# STM32f407layout.net
KiCad netlist of a schematic drawn in EAGLE
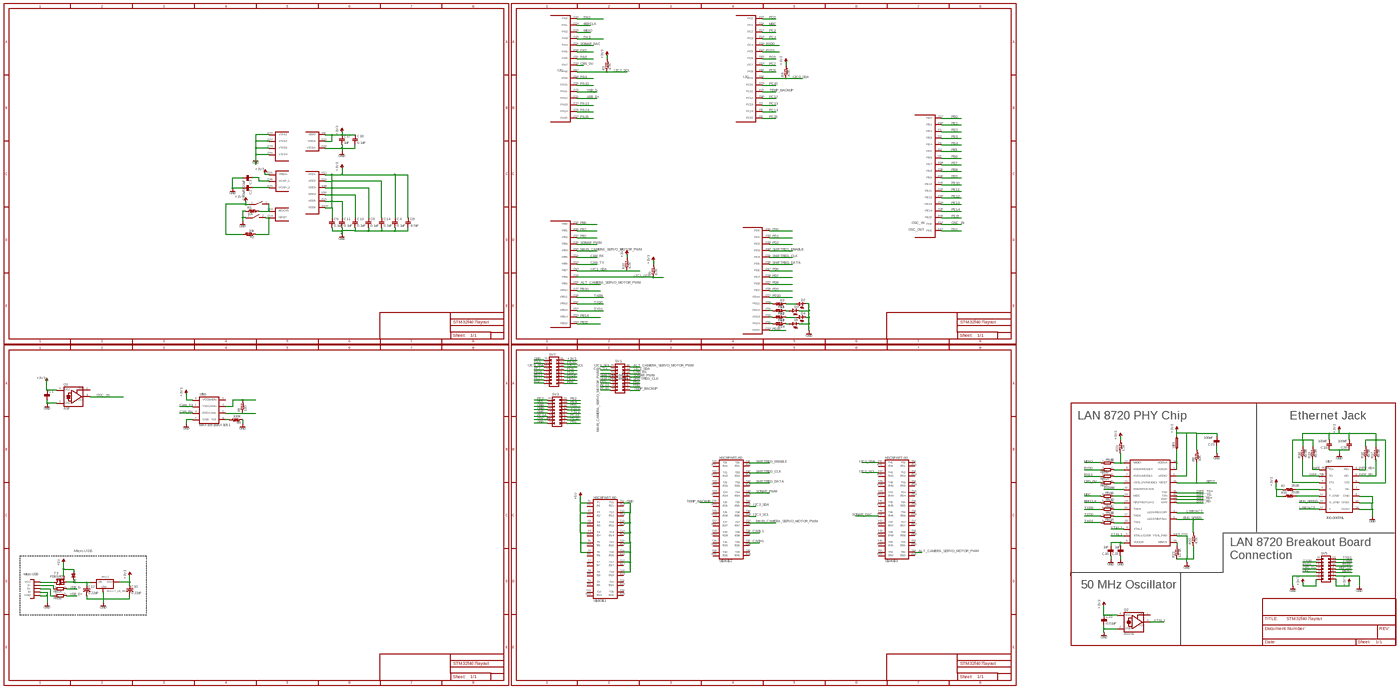
[diagram p0: schematic, sheet 1, overview]
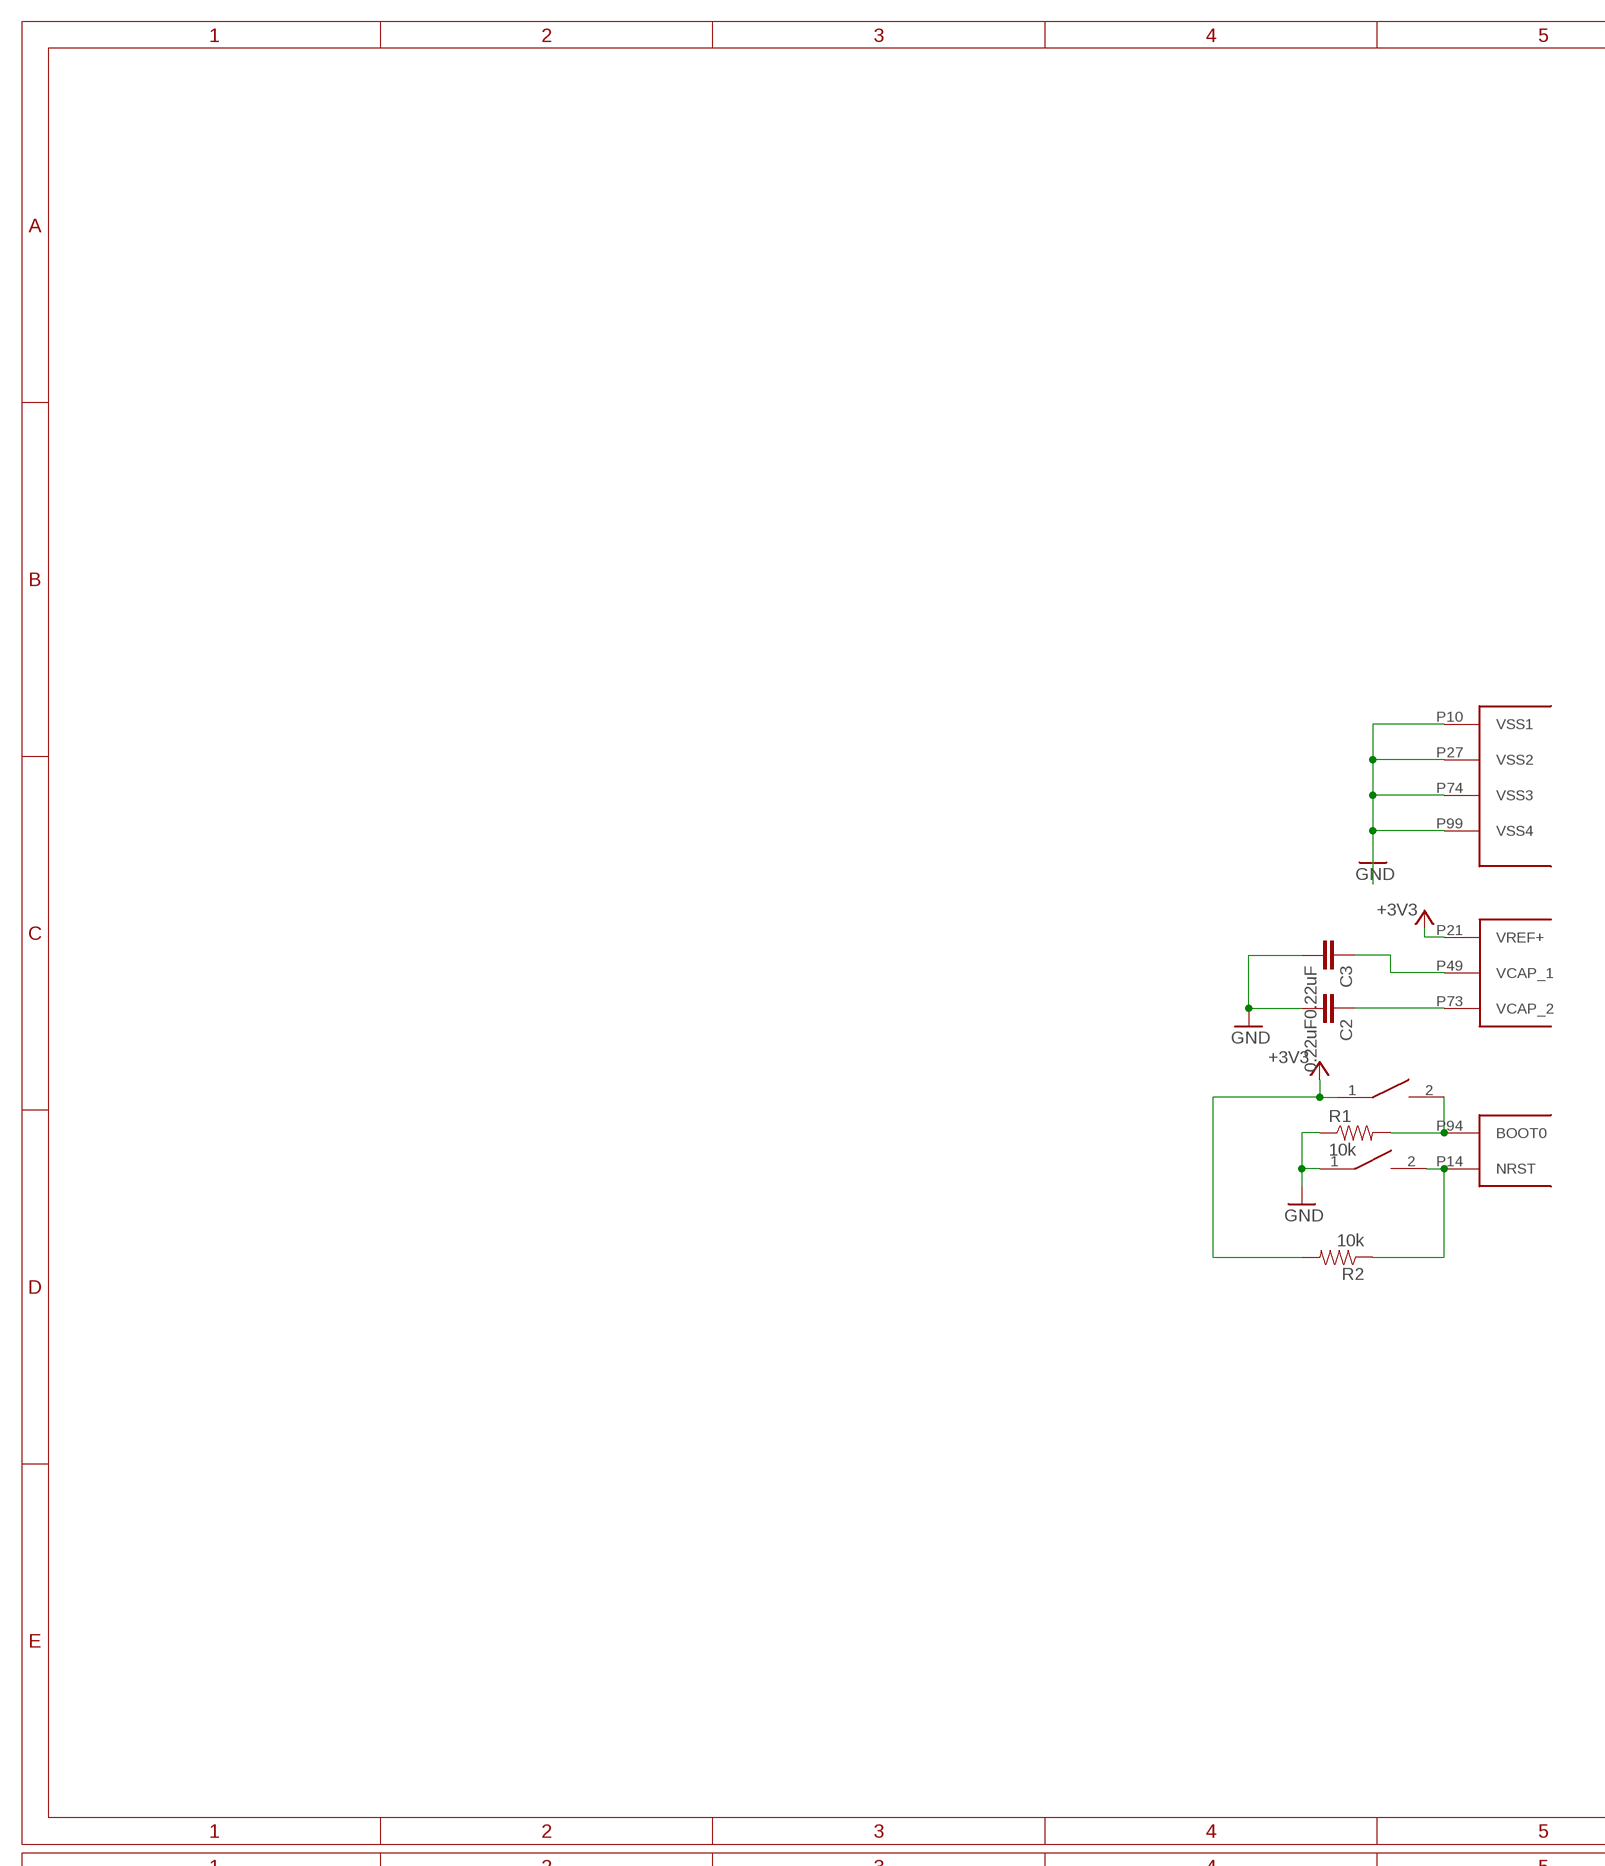
[diagram p1: schematic, sheet 1, part 1 of 7]
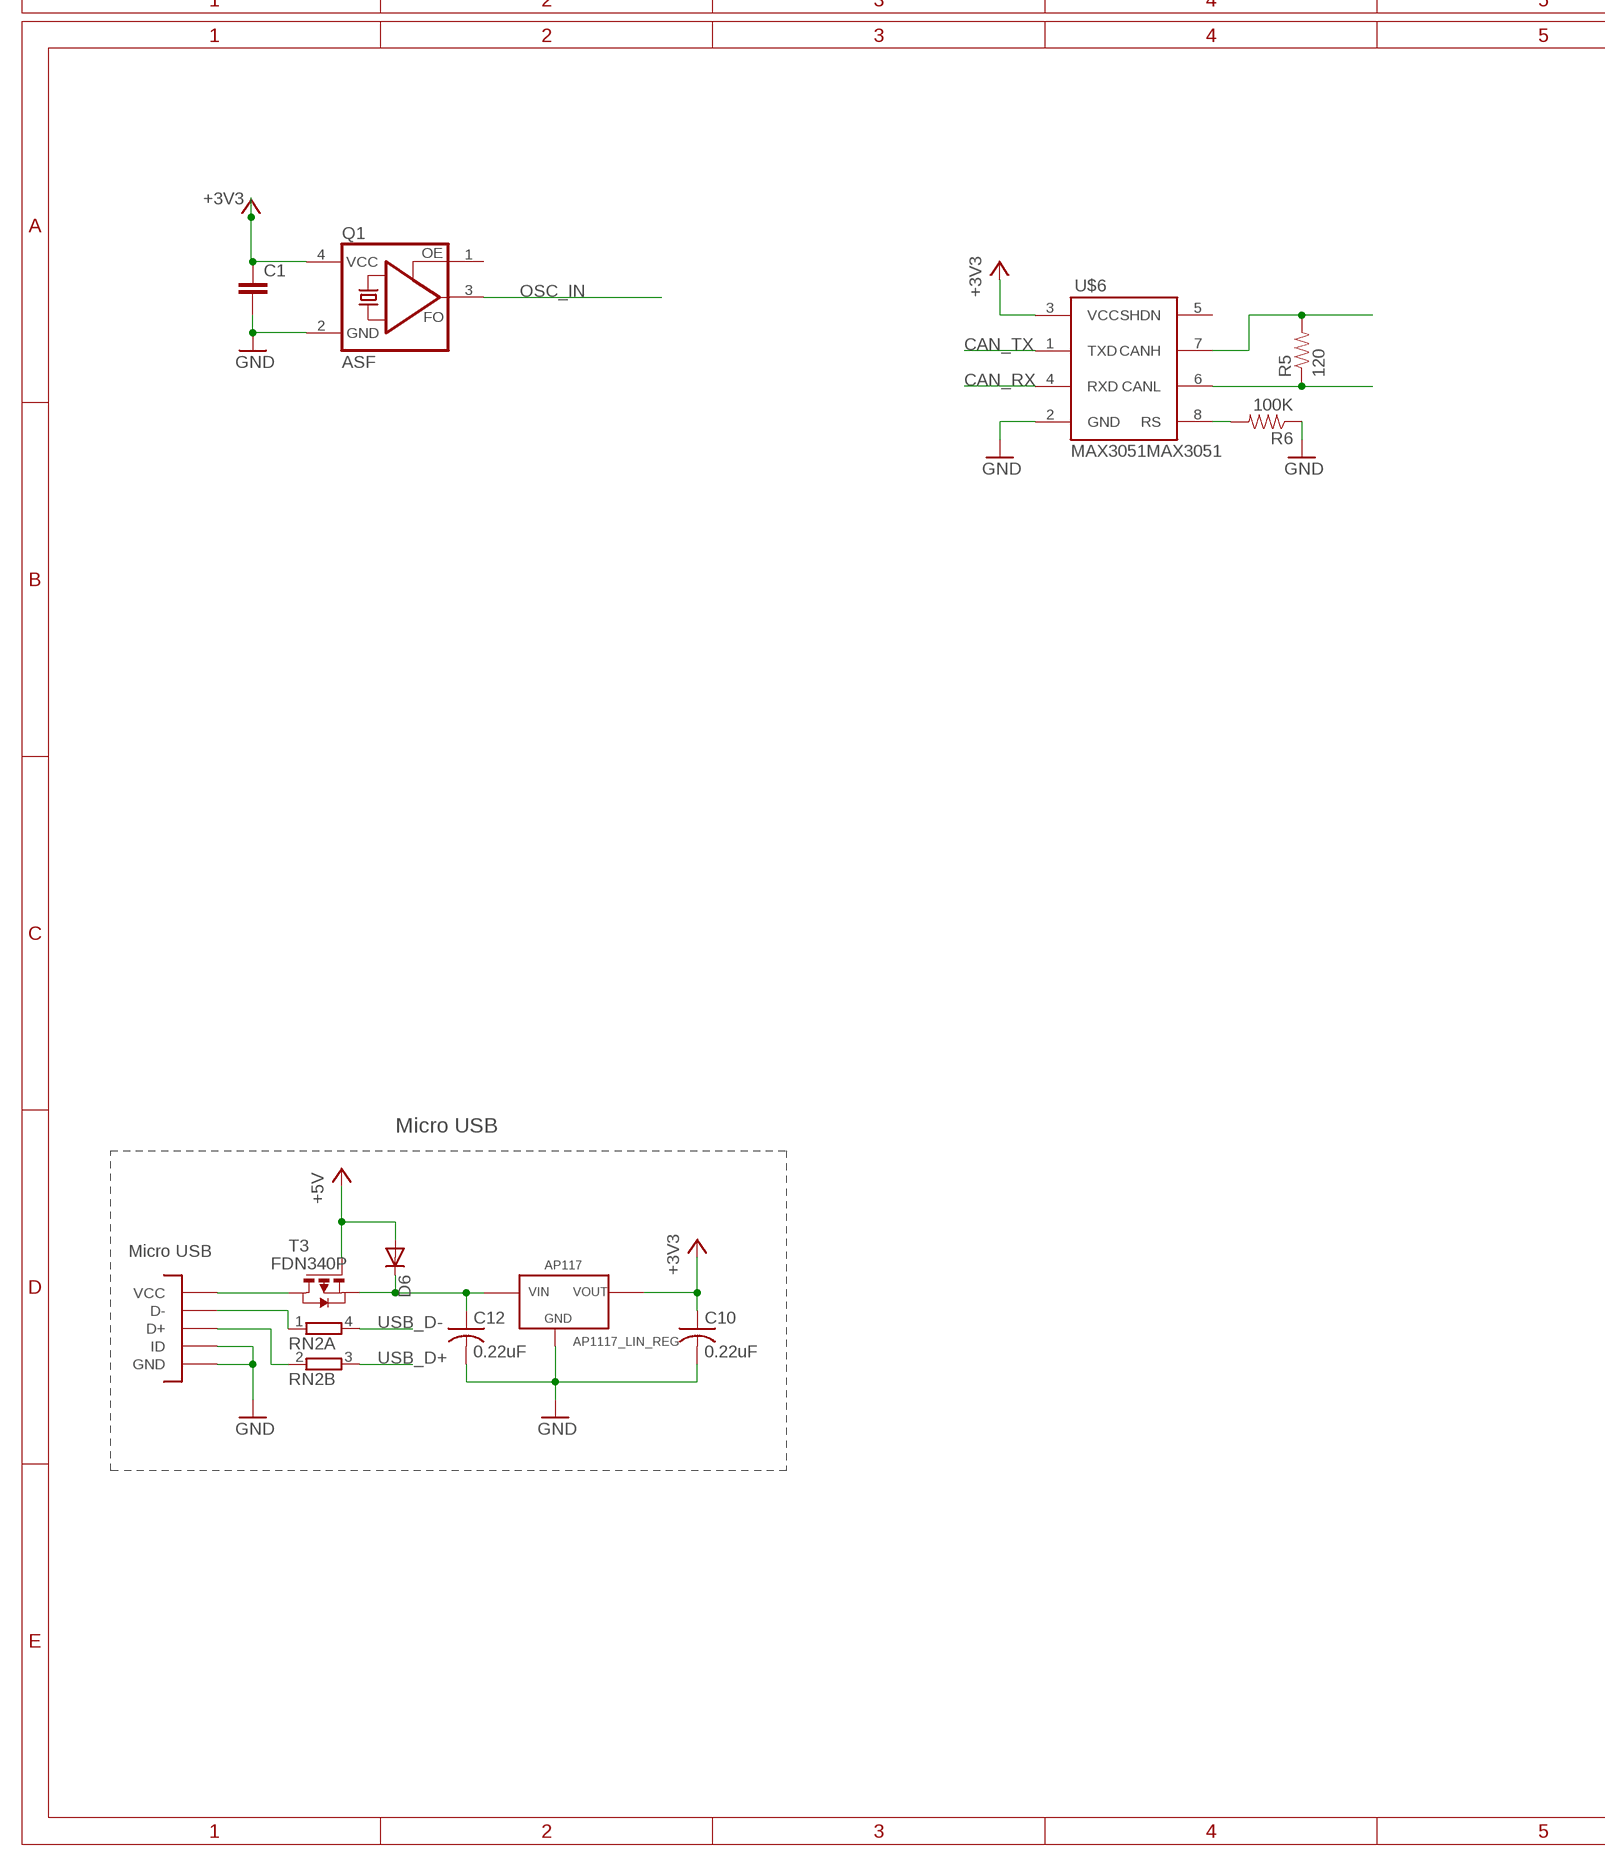
[diagram p2: schematic, sheet 1, part 2 of 7]
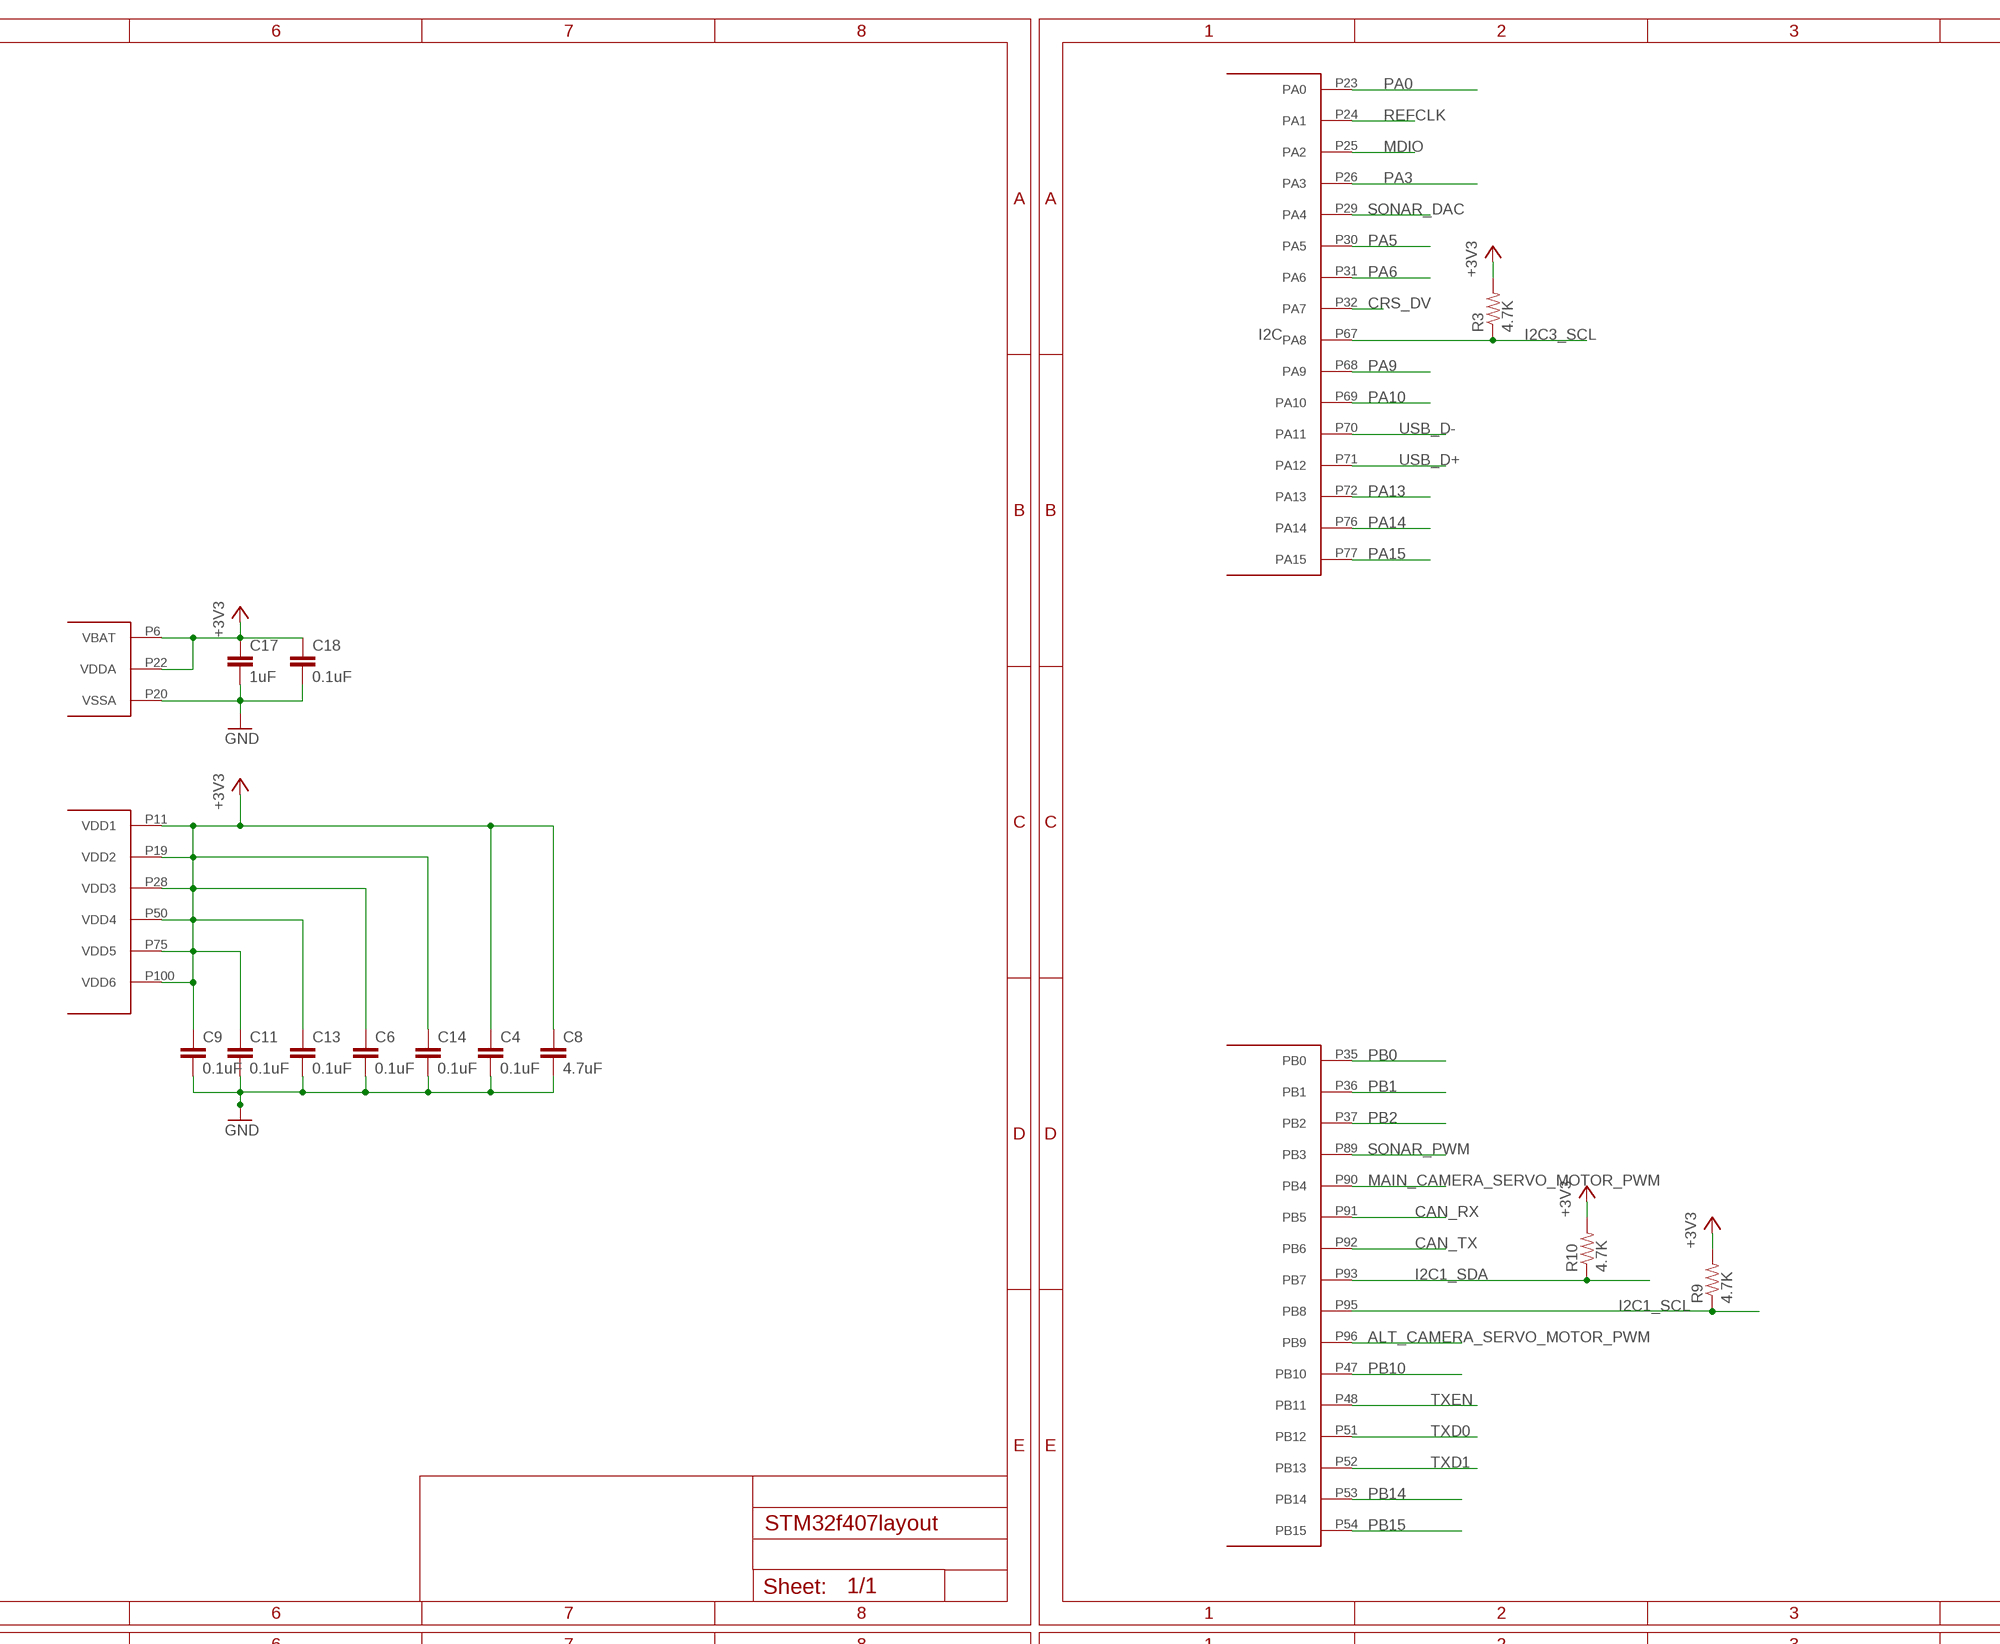
[diagram p3: schematic, sheet 1, part 3 of 7]
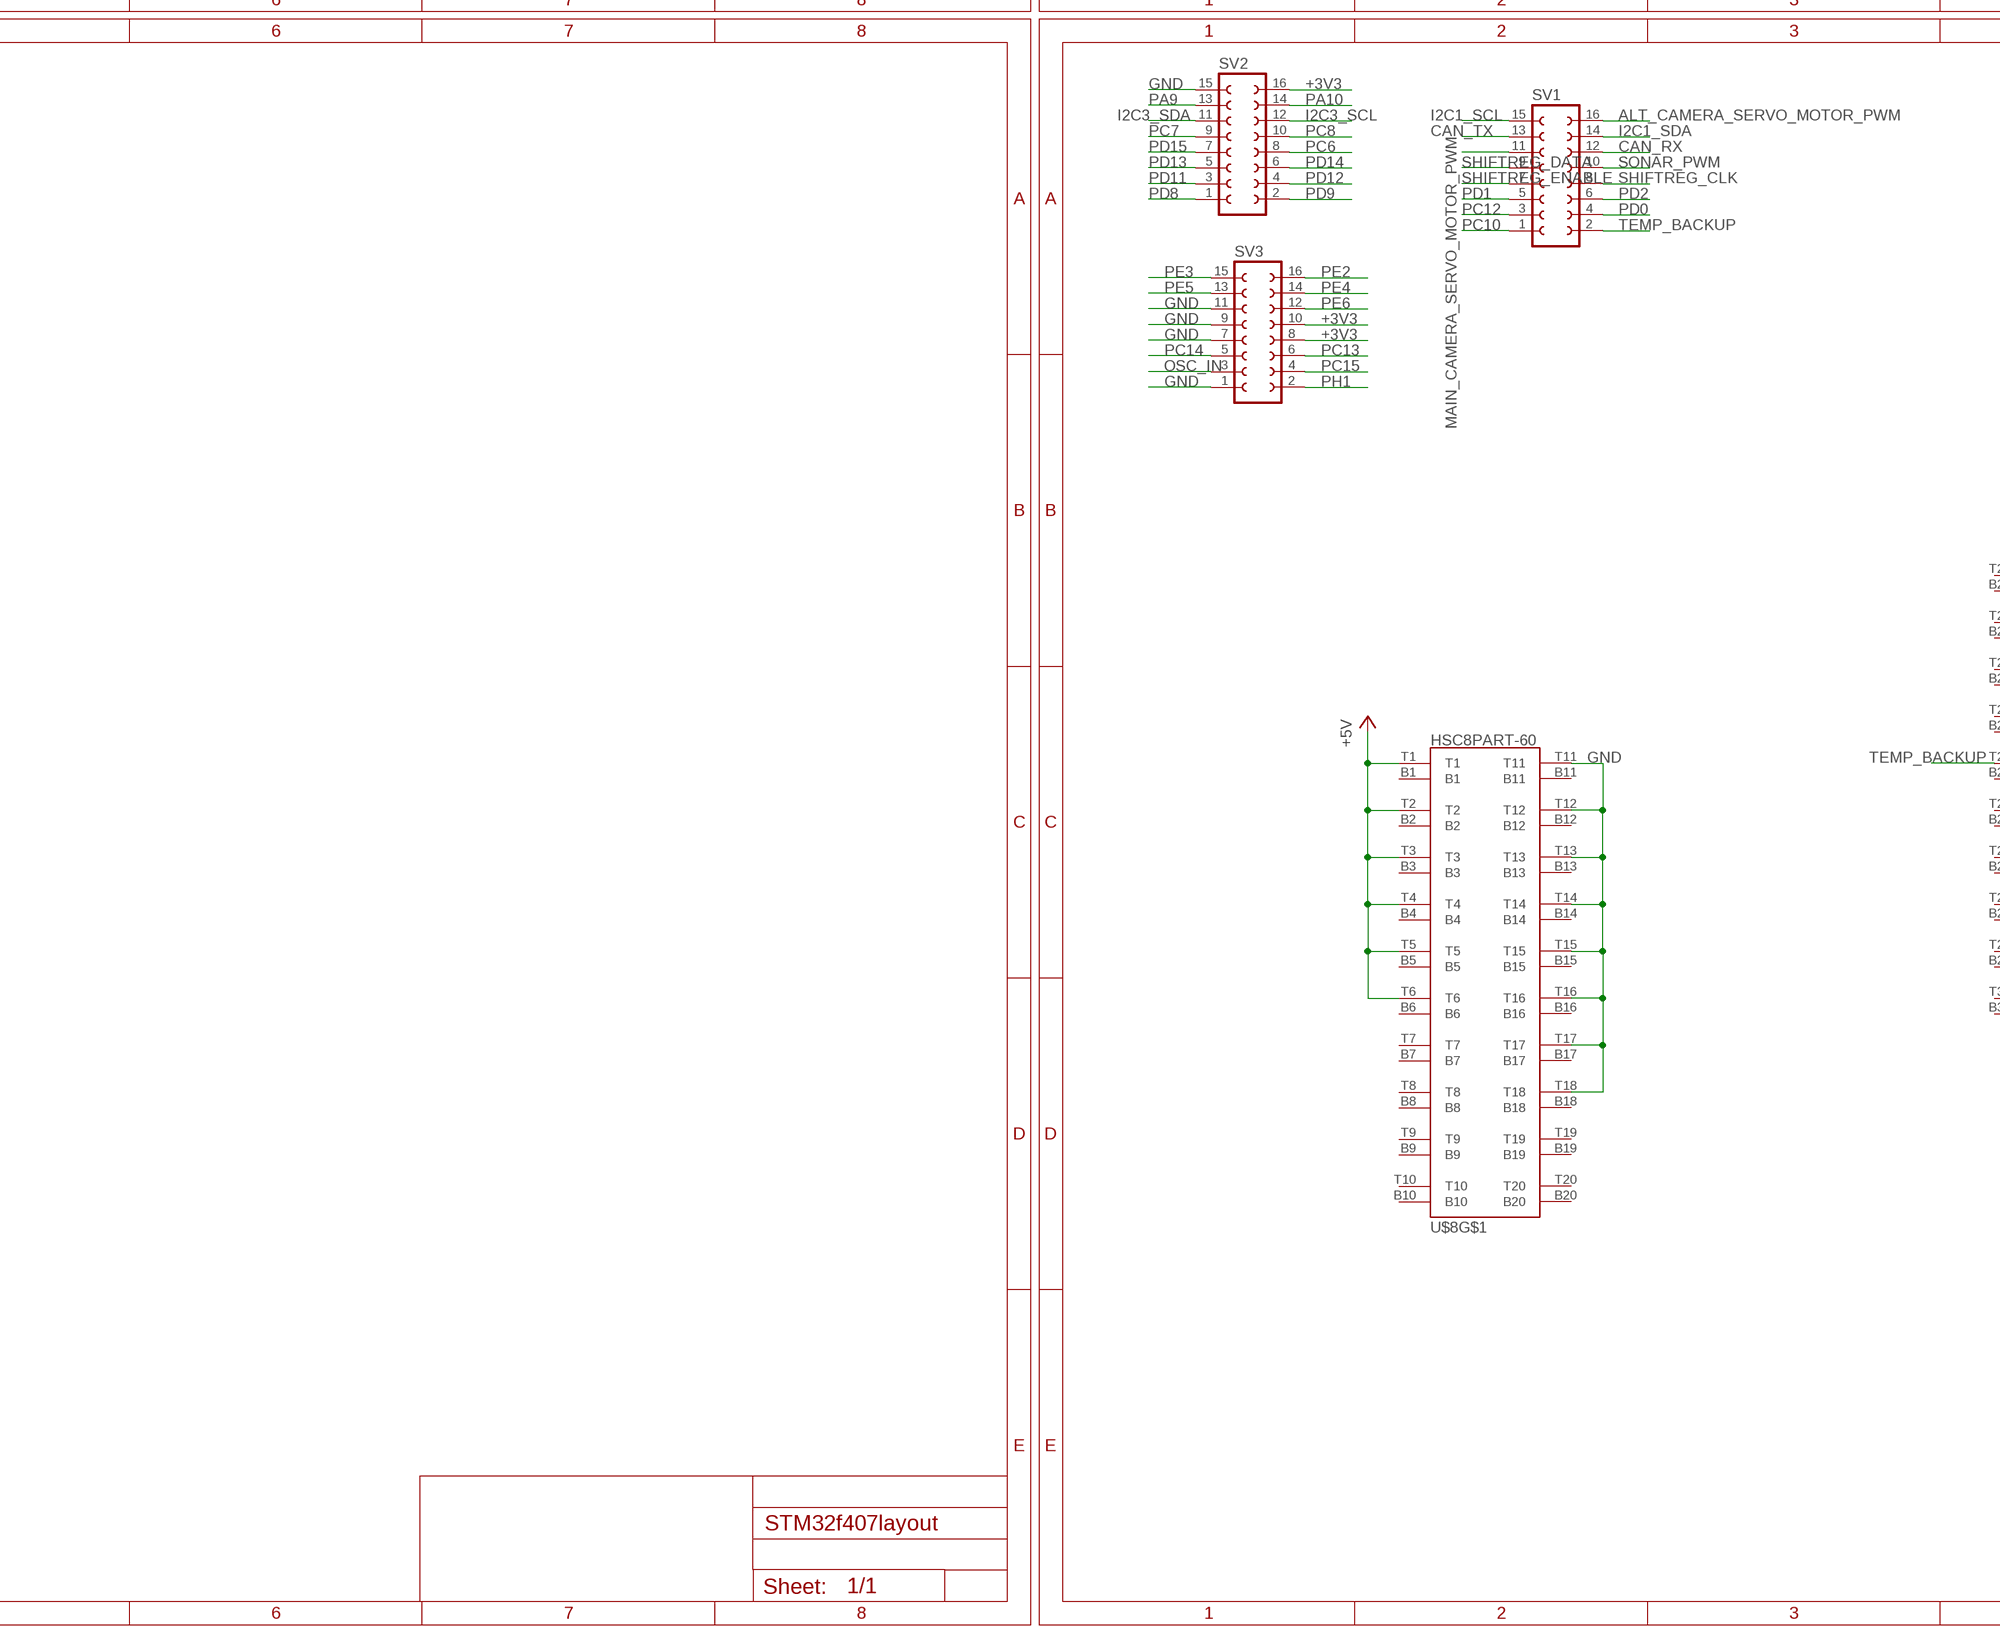
[diagram p4: schematic, sheet 1, part 4 of 7]
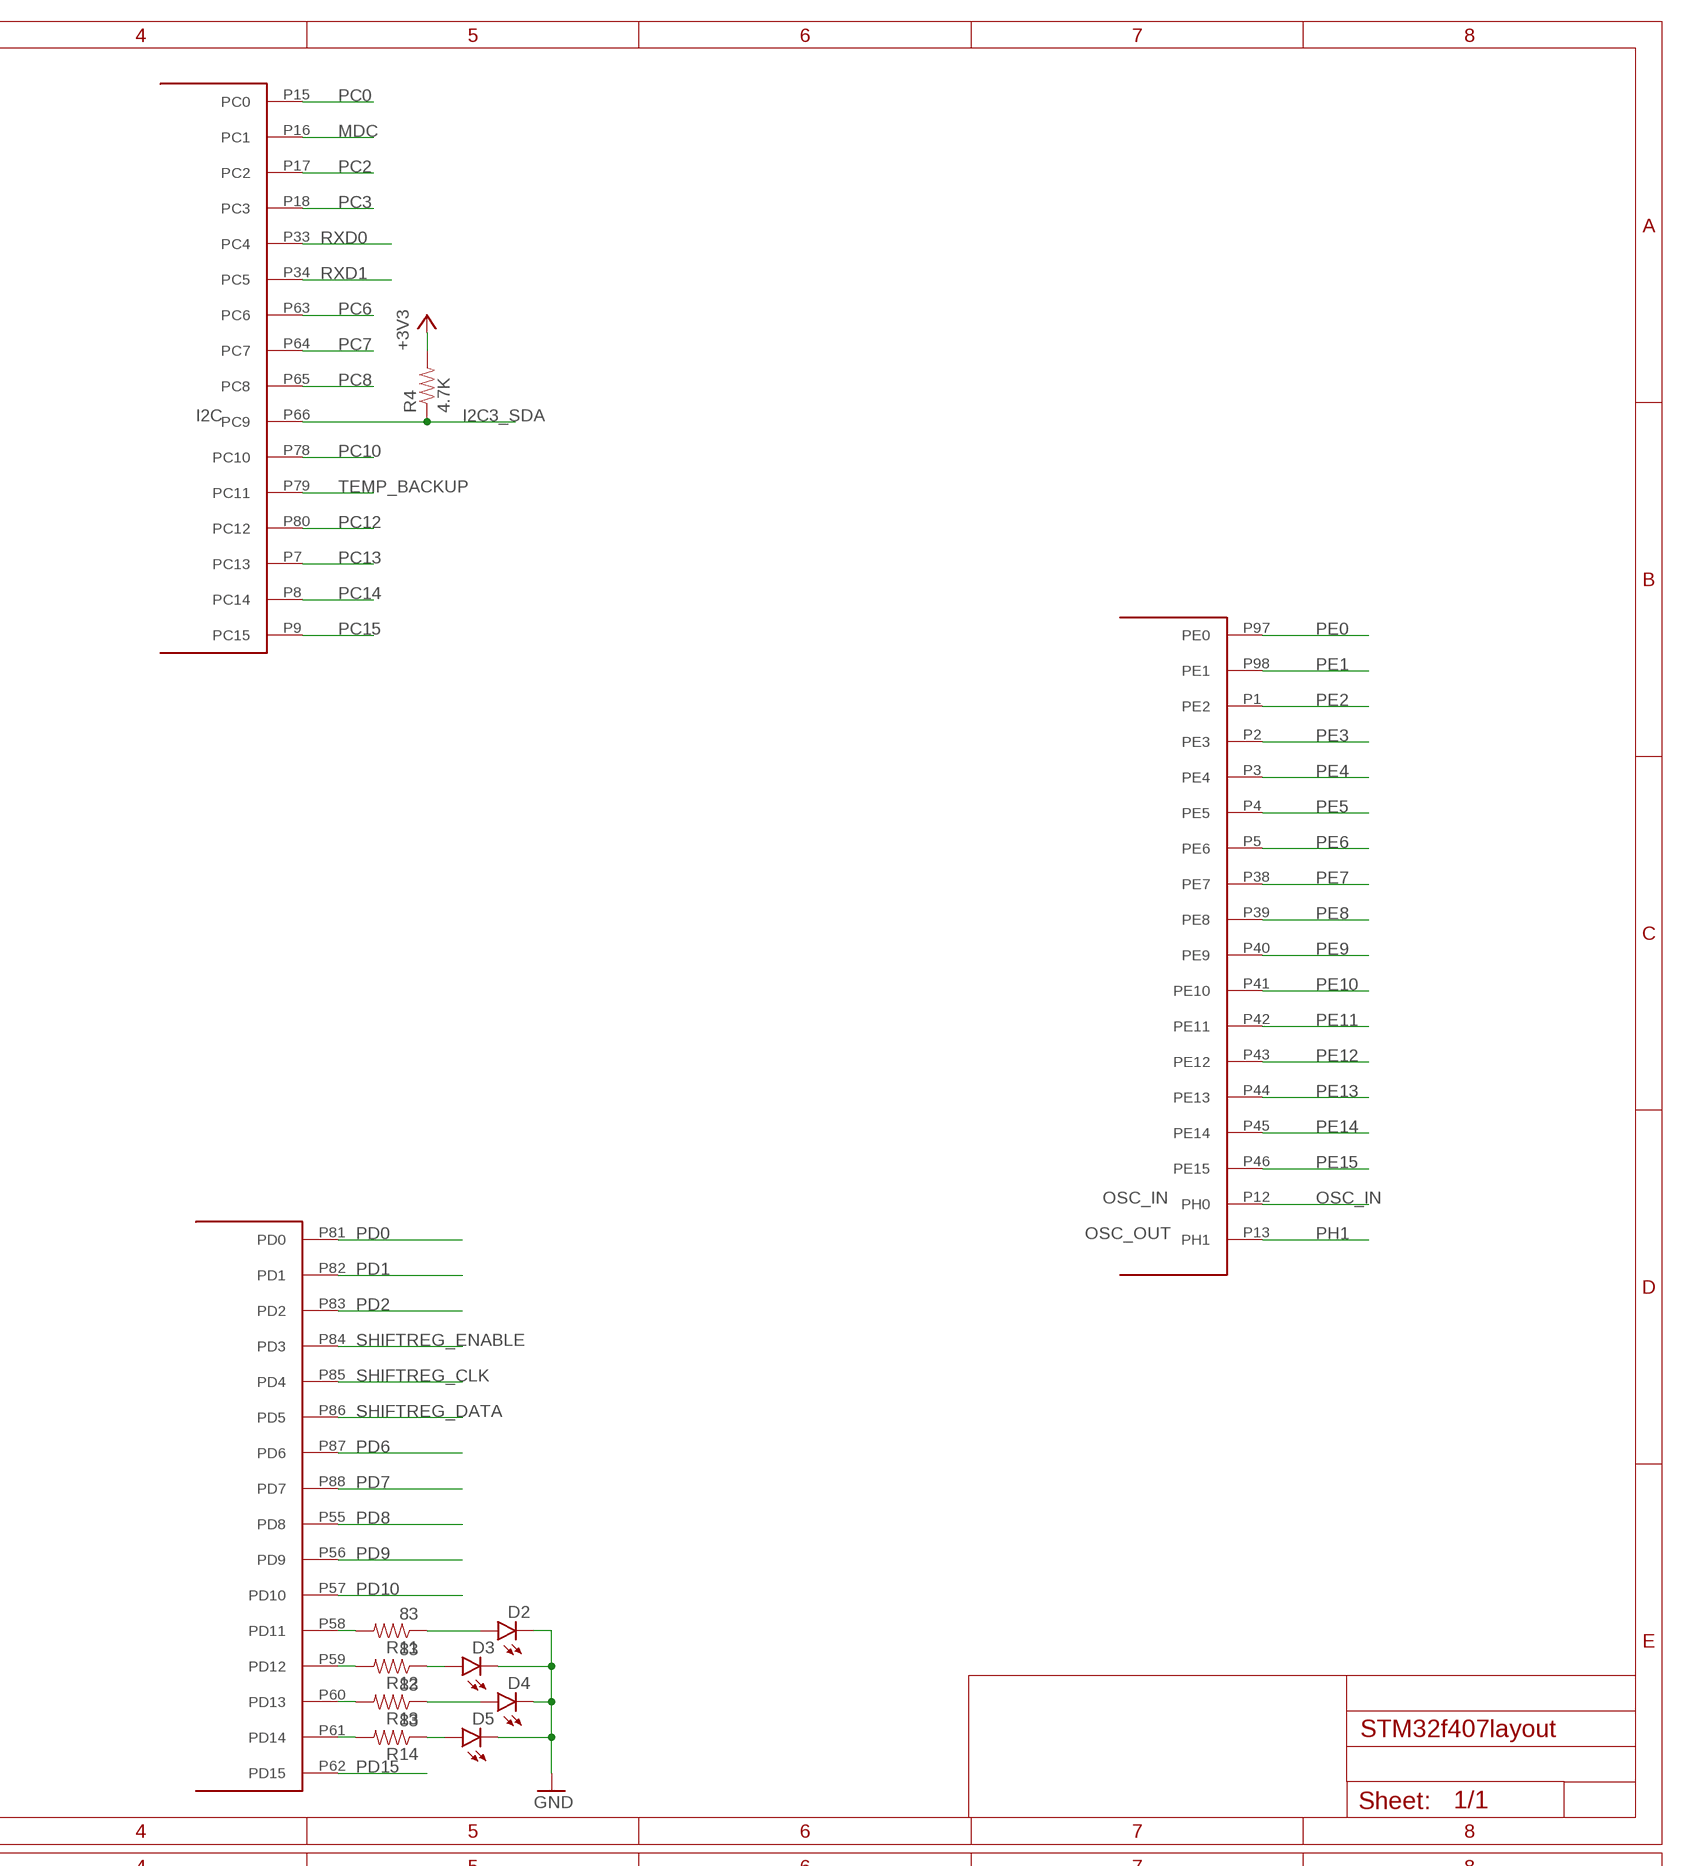
[diagram p5: schematic, sheet 1, part 5 of 7]
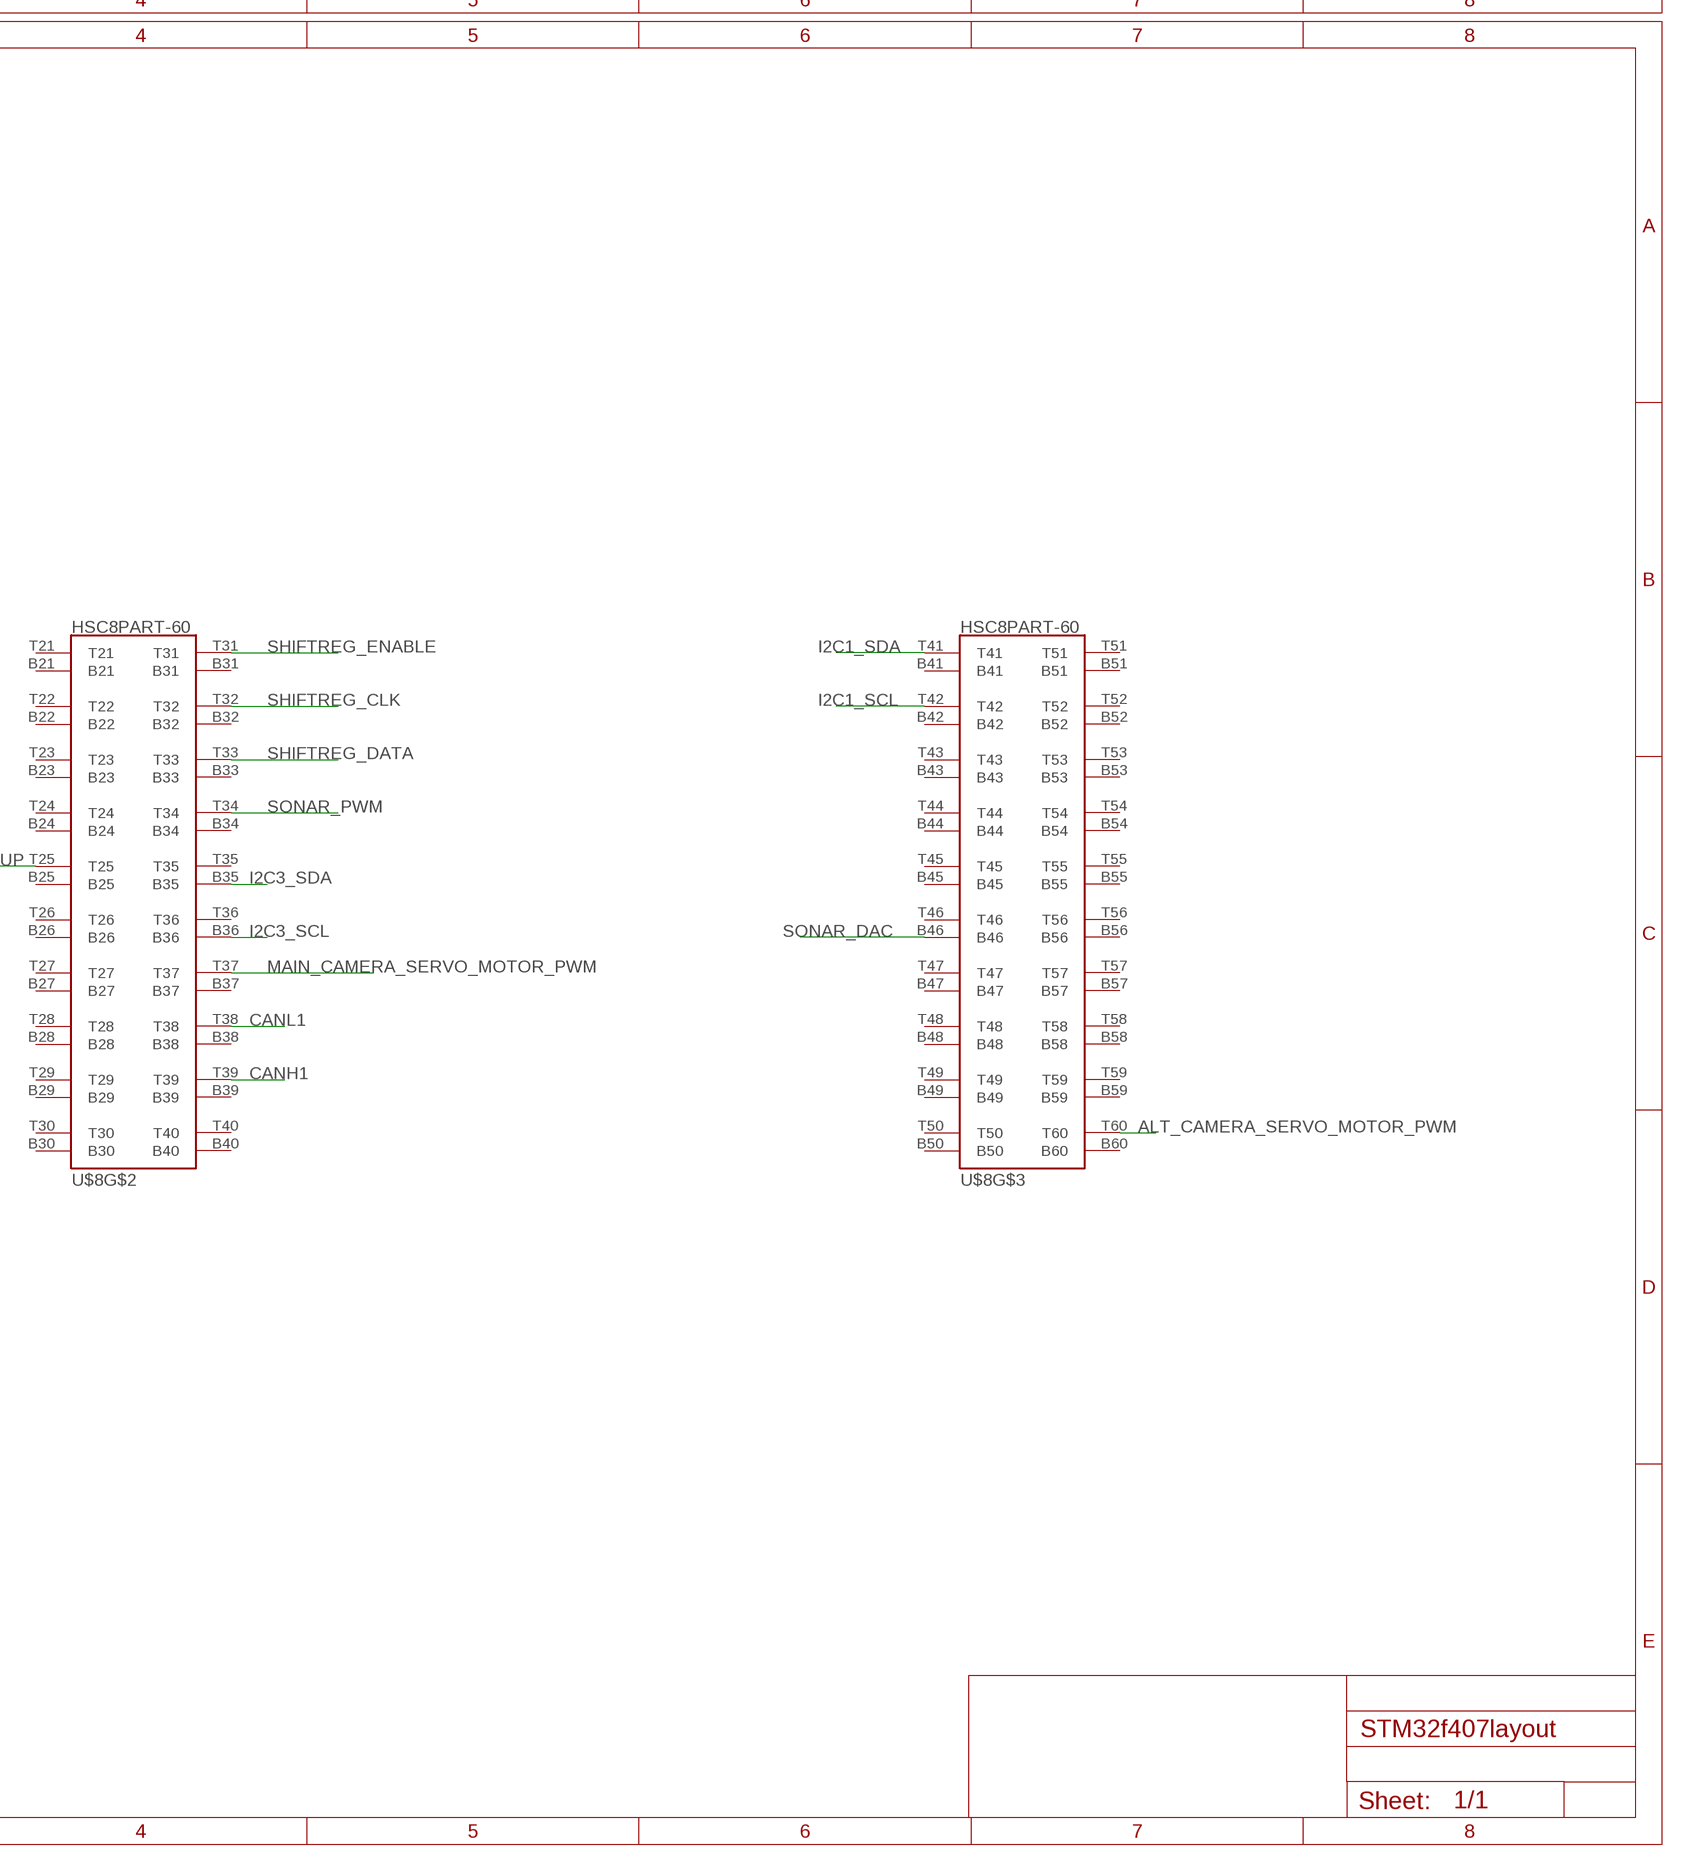
[diagram p6: schematic, sheet 1, part 6 of 7]
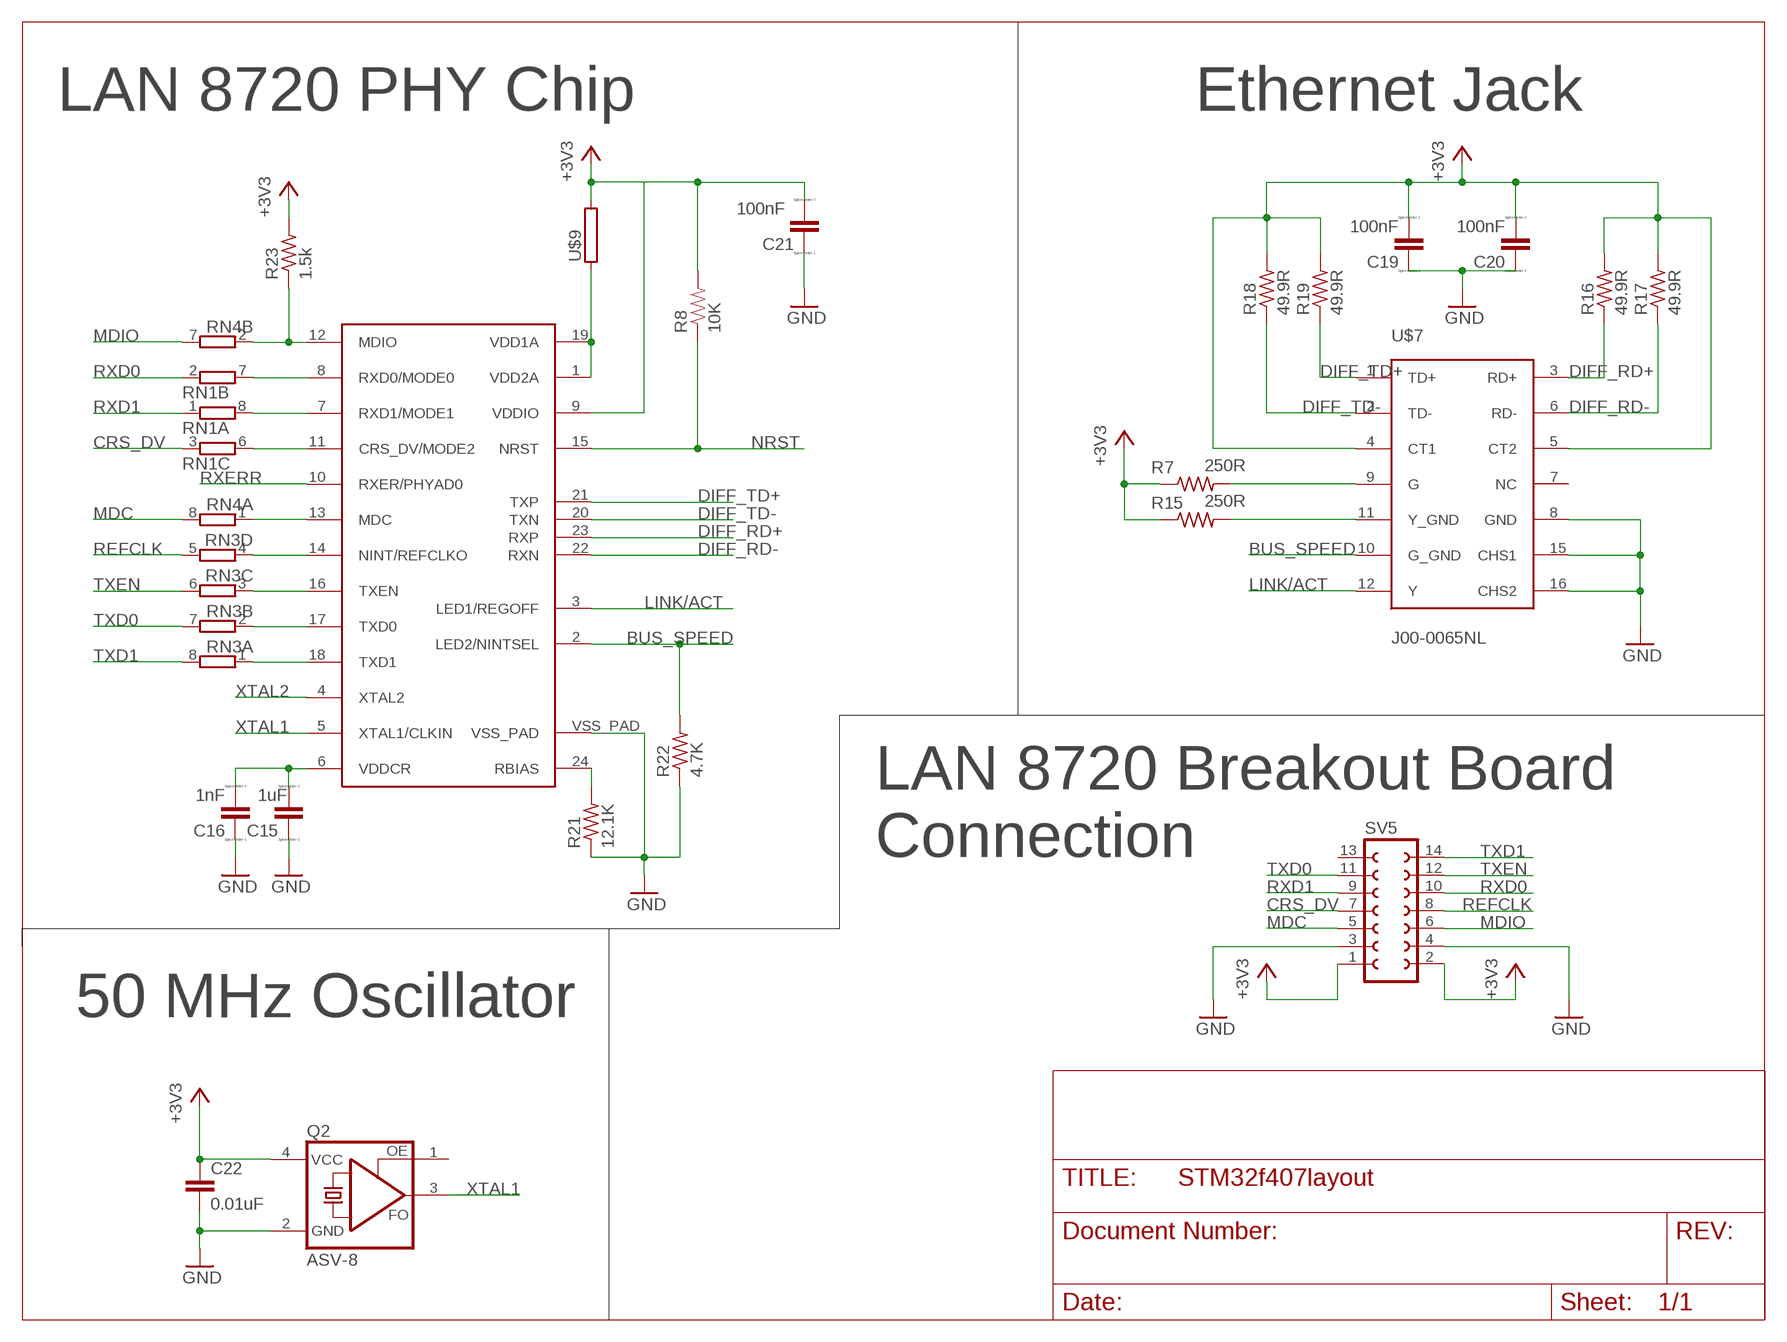
[diagram p7: schematic, sheet 1, part 7 of 7]

(export (version "E")
  (design (tool "Eeschema 10.0.6"))
  (components
    (comp (ref "C1")
      (value "CAP0603-CAP")
      (footprint "eagle-import:0603-CAP")
      (libsource (lib "eagle-import") (part "CAP0603-CAP"))
    )
    (comp (ref "C2")
      (value "0.22uF")
      (footprint "eagle-import:0603-CAP")
      (libsource (lib "eagle-import") (part "CAP0603-CAP"))
    )
    (comp (ref "C3")
      (value "0.22uF")
      (footprint "eagle-import:0603-CAP")
      (libsource (lib "eagle-import") (part "CAP0603-CAP"))
    )
    (comp (ref "C4")
      (value "0.1uF")
      (footprint "eagle-import:0603-CAP")
      (libsource (lib "eagle-import") (part "CAP0603-CAP"))
    )
    (comp (ref "C6")
      (value "0.1uF")
      (footprint "eagle-import:0603-CAP")
      (libsource (lib "eagle-import") (part "CAP0603-CAP"))
    )
    (comp (ref "C8")
      (value "4.7uF")
      (footprint "eagle-import:0603-CAP")
      (libsource (lib "eagle-import") (part "CAP0603-CAP"))
    )
    (comp (ref "C9")
      (value "0.1uF")
      (footprint "eagle-import:0603-CAP")
      (libsource (lib "eagle-import") (part "CAP0603-CAP"))
    )
    (comp (ref "C10")
      (value "0.22uF")
      (footprint "eagle-import:C0603")
      (libsource (lib "eagle-import") (part "C-USC0603"))
    )
    (comp (ref "C11")
      (value "0.1uF")
      (footprint "eagle-import:0603-CAP")
      (libsource (lib "eagle-import") (part "CAP0603-CAP"))
    )
    (comp (ref "C12")
      (value "0.22uF")
      (footprint "eagle-import:C0603")
      (libsource (lib "eagle-import") (part "C-USC0603"))
    )
    (comp (ref "C13")
      (value "0.1uF")
      (footprint "eagle-import:0603-CAP")
      (libsource (lib "eagle-import") (part "CAP0603-CAP"))
    )
    (comp (ref "C14")
      (value "0.1uF")
      (footprint "eagle-import:0603-CAP")
      (libsource (lib "eagle-import") (part "CAP0603-CAP"))
    )
    (comp (ref "C15")
      (value "1uF")
      (footprint "eagle-import:C0603")
      (libsource (lib "eagle-import") (part "CC0603"))
    )
    (comp (ref "C16")
      (value "1nF")
      (footprint "eagle-import:C0603")
      (libsource (lib "eagle-import") (part "CC0603"))
    )
    (comp (ref "C17")
      (value "1uF")
      (footprint "eagle-import:0603-CAP")
      (libsource (lib "eagle-import") (part "CAP0603-CAP"))
    )
    (comp (ref "C18")
      (value "0.1uF")
      (footprint "eagle-import:0603-CAP")
      (libsource (lib "eagle-import") (part "CAP0603-CAP"))
    )
    (comp (ref "C19")
      (value "100nF")
      (footprint "eagle-import:C0603")
      (libsource (lib "eagle-import") (part "CC0603"))
    )
    (comp (ref "C20")
      (value "100nF")
      (footprint "eagle-import:C0603")
      (libsource (lib "eagle-import") (part "CC0603"))
    )
    (comp (ref "C21")
      (value "100nF")
      (footprint "eagle-import:C0603")
      (libsource (lib "eagle-import") (part "CC0603"))
    )
    (comp (ref "C22")
      (value "0.01uF")
      (footprint "eagle-import:C0603")
      (libsource (lib "eagle-import") (part "C-EUC0603"))
    )
    (comp (ref "D2")
      (value "LED0603")
      (footprint "eagle-import:LED-0603")
      (libsource (lib "eagle-import") (part "LED0603"))
    )
    (comp (ref "D3")
      (value "LED0603")
      (footprint "eagle-import:LED-0603")
      (libsource (lib "eagle-import") (part "LED0603"))
    )
    (comp (ref "D4")
      (value "LED0603")
      (footprint "eagle-import:LED-0603")
      (libsource (lib "eagle-import") (part "LED0603"))
    )
    (comp (ref "D5")
      (value "LED0603")
      (footprint "eagle-import:LED-0603")
      (libsource (lib "eagle-import") (part "LED0603"))
    )
    (comp (ref "D6")
      (value "DIODE-DO-214AC")
      (footprint "eagle-import:DO-214AC")
      (libsource (lib "eagle-import") (part "DIODE-DO-214AC"))
    )
    (comp (ref "Q1")
      (value "ASF")
      (footprint "eagle-import:ASF")
      (libsource (lib "eagle-import") (part "ASF"))
    )
    (comp (ref "Q2")
      (value "ASV-8")
      (footprint "eagle-import:ASF")
      (libsource (lib "eagle-import") (part "MicroBoard_ASF"))
    )
    (comp (ref "R1")
      (value "10k")
      (footprint "eagle-import:0603-RES")
      (libsource (lib "eagle-import") (part "RESISTOR0603-RES"))
    )
    (comp (ref "R2")
      (value "10k")
      (footprint "eagle-import:0603-RES")
      (libsource (lib "eagle-import") (part "RESISTOR0603-RES"))
    )
    (comp (ref "R3")
      (value "4.7K")
      (footprint "eagle-import:0603-RES")
      (libsource (lib "eagle-import") (part "RESISTOR0603-RES"))
    )
    (comp (ref "R4")
      (value "4.7K")
      (footprint "eagle-import:0603-RES")
      (libsource (lib "eagle-import") (part "RESISTOR0603-RES"))
    )
    (comp (ref "R5")
      (value "120")
      (footprint "eagle-import:0603-RES")
      (libsource (lib "eagle-import") (part "RESISTOR0603-RES"))
    )
    (comp (ref "R6")
      (value "100K")
      (footprint "eagle-import:0603-RES")
      (libsource (lib "eagle-import") (part "RESISTOR0603-RES"))
    )
    (comp (ref "R7")
      (value "250R")
      (footprint "eagle-import:R0603")
      (libsource (lib "eagle-import") (part "R-US_R0603"))
    )
    (comp (ref "R8")
      (value "10K")
      (footprint "eagle-import:0603-RES")
      (libsource (lib "eagle-import") (part "RESISTOR0603-RES"))
    )
    (comp (ref "R9")
      (value "4.7K")
      (footprint "eagle-import:0603-RES")
      (libsource (lib "eagle-import") (part "RESISTOR0603-RES"))
    )
    (comp (ref "R10")
      (value "4.7K")
      (footprint "eagle-import:0603-RES")
      (libsource (lib "eagle-import") (part "RESISTOR0603-RES"))
    )
    (comp (ref "R11")
      (value "83")
      (footprint "eagle-import:0603-RES")
      (libsource (lib "eagle-import") (part "RESISTOR0603-RES"))
    )
    (comp (ref "R12")
      (value "83")
      (footprint "eagle-import:0603-RES")
      (libsource (lib "eagle-import") (part "RESISTOR0603-RES"))
    )
    (comp (ref "R13")
      (value "83")
      (footprint "eagle-import:0603-RES")
      (libsource (lib "eagle-import") (part "RESISTOR0603-RES"))
    )
    (comp (ref "R14")
      (value "83")
      (footprint "eagle-import:0603-RES")
      (libsource (lib "eagle-import") (part "RESISTOR0603-RES"))
    )
    (comp (ref "R15")
      (value "250R")
      (footprint "eagle-import:R0603")
      (libsource (lib "eagle-import") (part "R-US_R0603"))
    )
    (comp (ref "R16")
      (value "49.9R")
      (footprint "eagle-import:R0603")
      (libsource (lib "eagle-import") (part "R-US_R0603"))
    )
    (comp (ref "R17")
      (value "49.9R")
      (footprint "eagle-import:R0603")
      (libsource (lib "eagle-import") (part "R-US_R0603"))
    )
    (comp (ref "R18")
      (value "49.9R")
      (footprint "eagle-import:R0603")
      (libsource (lib "eagle-import") (part "R-US_R0603"))
    )
    (comp (ref "R19")
      (value "49.9R")
      (footprint "eagle-import:R0603")
      (libsource (lib "eagle-import") (part "R-US_R0603"))
    )
    (comp (ref "R21")
      (value "12.1K")
      (footprint "eagle-import:R0603")
      (libsource (lib "eagle-import") (part "R-US_R0603"))
    )
    (comp (ref "R22")
      (value "4.7K")
      (footprint "eagle-import:R0603")
      (libsource (lib "eagle-import") (part "R-US_R0603"))
    )
    (comp (ref "R23")
      (value "1.5k")
      (footprint "eagle-import:R0603")
      (libsource (lib "eagle-import") (part "R-US_R0603"))
    )
    (comp (ref "RN1")
      (value "4R-NCAY16")
      (footprint "eagle-import:CAY16")
      (libsource (lib "eagle-import") (part "4R-NCAY16"))
    )
    (comp (ref "RN2")
      (value "2R-NEXBV4V")
      (footprint "eagle-import:EXBV4V")
      (fields (field (name "MF") "Rohm Semiconductor") (field (name "MPN") "MNR12ERAPJ220"))
      (libsource (lib "eagle-import") (part "2R-NEXBV4V"))
    )
    (comp (ref "RN3")
      (value "4R-NCAY16")
      (footprint "eagle-import:CAY16")
      (libsource (lib "eagle-import") (part "4R-NCAY16"))
    )
    (comp (ref "RN4")
      (value "4R-NCAY16")
      (footprint "eagle-import:CAY16")
      (libsource (lib "eagle-import") (part "4R-NCAY16"))
    )
    (comp (ref "SV1")
      (value "FE08-2")
      (footprint "eagle-import:FE08-2")
      (libsource (lib "eagle-import") (part "FE08-2"))
    )
    (comp (ref "SV2")
      (value "FE08-2")
      (footprint "eagle-import:FE08-2")
      (libsource (lib "eagle-import") (part "FE08-2"))
    )
    (comp (ref "SV3")
      (value "FE08-2")
      (footprint "eagle-import:FE08-2")
      (libsource (lib "eagle-import") (part "FE08-2"))
    )
    (comp (ref "SV5")
      (value "FE07-2")
      (footprint "eagle-import:FE07-2")
      (libsource (lib "eagle-import") (part "FE07-2"))
    )
    (comp (ref "T3")
      (value "FDN340P")
      (footprint "eagle-import:SOT-23")
      (libsource (lib "eagle-import") (part "FDN340P"))
    )
    (comp (ref "T4")
      (value "AP1117_LIN_REG")
      (footprint "eagle-import:SOT223")
      (libsource (lib "eagle-import") (part "AP1117_LIN_REG"))
    )
    (comp (ref "U$1")
      (value "STM32F4")
      (footprint "eagle-import:LQFP100")
      (libsource (lib "eagle-import") (part "STM32F4"))
    )
    (comp (ref "U$2")
      (value "SWITCH")
      (footprint "eagle-import:SW_2512")
      (libsource (lib "eagle-import") (part "SWITCH"))
    )
    (comp (ref "U$3")
      (value "SWITCH")
      (footprint "eagle-import:SW_2512")
      (libsource (lib "eagle-import") (part "SWITCH"))
    )
    (comp (ref "U$4")
      (value "LAN8720LAN8720")
      (footprint "eagle-import:24-QFN")
      (libsource (lib "eagle-import") (part "LAN8720LAN8720"))
    )
    (comp (ref "U$5")
      (value "MICROUSB")
      (footprint "eagle-import:MICRO_B")
      (libsource (lib "eagle-import") (part "MICROUSB"))
    )
    (comp (ref "U$6")
      (value "MAX3051MAX3051")
      (footprint "eagle-import:SOT23-8L")
      (libsource (lib "eagle-import") (part "MAX3051MAX3051"))
    )
    (comp (ref "U$7")
      (value "J00-0065NL")
      (footprint "eagle-import:J00-0065NL")
      (libsource (lib "eagle-import") (part "J00-0065NL"))
    )
    (comp (ref "U$8")
      (value "HSC8PART-60")
      (footprint "eagle-import:HSC8-60PINOUUT")
      (libsource (lib "eagle-import") (part "HSC8PART-60"))
    )
    (comp (ref "U$9")
      (value "553-2382-1-ND")
      (footprint "eagle-import:0603")
      (libsource (lib "eagle-import") (part "553-2382-1-ND"))
    )
  )
  (nets
    (net (code "1") (name "+3V3") (class "Default")
      (node (ref "C1") (pin "1") (pinfunction "1_1") (pintype "passive"))
      (node (ref "C10") (pin "1") (pinfunction "1_1") (pintype "passive"))
      (node (ref "C11") (pin "1") (pinfunction "1_1") (pintype "passive"))
      (node (ref "C13") (pin "1") (pinfunction "1_1") (pintype "passive"))
      (node (ref "C14") (pin "1") (pinfunction "1_1") (pintype "passive"))
      (node (ref "C17") (pin "1") (pinfunction "1_1") (pintype "passive"))
      (node (ref "C18") (pin "1") (pinfunction "1_1") (pintype "passive"))
      (node (ref "C19") (pin "2") (pinfunction "2_2") (pintype "passive"))
      (node (ref "C20") (pin "2") (pinfunction "2_2") (pintype "passive"))
      (node (ref "C21") (pin "2") (pinfunction "2_2") (pintype "passive"))
      (node (ref "C22") (pin "1") (pinfunction "1_1") (pintype "passive"))
      (node (ref "C4") (pin "1") (pinfunction "1_1") (pintype "passive"))
      (node (ref "C6") (pin "1") (pinfunction "1_1") (pintype "passive"))
      (node (ref "C8") (pin "1") (pinfunction "1_1") (pintype "passive"))
      (node (ref "C9") (pin "1") (pinfunction "1_1") (pintype "passive"))
      (node (ref "Q1") (pin "4") (pinfunction "VCC_4") (pintype "power_in"))
      (node (ref "Q2") (pin "4") (pinfunction "VCC_4") (pintype "power_in"))
      (node (ref "R10") (pin "2") (pinfunction "2_2") (pintype "passive"))
      (node (ref "R15") (pin "1") (pinfunction "1_1") (pintype "passive"))
      (node (ref "R16") (pin "2") (pinfunction "2_2") (pintype "passive"))
      (node (ref "R17") (pin "2") (pinfunction "2_2") (pintype "passive"))
      (node (ref "R18") (pin "2") (pinfunction "2_2") (pintype "passive"))
      (node (ref "R19") (pin "2") (pinfunction "2_2") (pintype "passive"))
      (node (ref "R2") (pin "2") (pinfunction "2_2") (pintype "passive"))
      (node (ref "R23") (pin "2") (pinfunction "2_2") (pintype "passive"))
      (node (ref "R3") (pin "2") (pinfunction "2_2") (pintype "passive"))
      (node (ref "R4") (pin "2") (pinfunction "2_2") (pintype "passive"))
      (node (ref "R7") (pin "1") (pinfunction "1_1") (pintype "passive"))
      (node (ref "R8") (pin "2") (pinfunction "2_2") (pintype "passive"))
      (node (ref "R9") (pin "2") (pinfunction "2_2") (pintype "passive"))
      (node (ref "SV2") (pin "16") (pinfunction "16_16") (pintype "passive"))
      (node (ref "SV3") (pin "10") (pinfunction "10_10") (pintype "passive"))
      (node (ref "SV3") (pin "8") (pinfunction "8_8") (pintype "passive"))
      (node (ref "SV5") (pin "1") (pinfunction "1_1") (pintype "passive"))
      (node (ref "SV5") (pin "2") (pinfunction "2_2") (pintype "passive"))
      (node (ref "T4") (pin "TAB") (pinfunction "VOUT_TAB") (pintype "output"))
      (node (ref "T4") (pin "VOUT") (pinfunction "VOUT_VOUT") (pintype "output"))
      (node (ref "U$1") (pin "P100") (pinfunction "VDD6_P100") (pintype "bidirectional"))
      (node (ref "U$1") (pin "P11") (pinfunction "VDD1_P11") (pintype "bidirectional"))
      (node (ref "U$1") (pin "P19") (pinfunction "VDD2_P19") (pintype "bidirectional"))
      (node (ref "U$1") (pin "P21") (pinfunction "VREF+_P21") (pintype "bidirectional"))
      (node (ref "U$1") (pin "P22") (pinfunction "VDDA_P22") (pintype "bidirectional"))
      (node (ref "U$1") (pin "P28") (pinfunction "VDD3_P28") (pintype "bidirectional"))
      (node (ref "U$1") (pin "P50") (pinfunction "VDD4_P50") (pintype "bidirectional"))
      (node (ref "U$1") (pin "P6") (pinfunction "VBAT_P6") (pintype "bidirectional"))
      (node (ref "U$1") (pin "P75") (pinfunction "VDD5_P75") (pintype "bidirectional"))
      (node (ref "U$3") (pin "1") (pinfunction "P$1_1") (pintype "bidirectional"))
      (node (ref "U$4") (pin "9") (pinfunction "VDDIO_9") (pintype "bidirectional"))
      (node (ref "U$6") (pin "3") (pinfunction "VCC_3") (pintype "bidirectional"))
      (node (ref "U$7") (pin "4") (pinfunction "CT1_4") (pintype "bidirectional"))
      (node (ref "U$7") (pin "5") (pinfunction "CT2_5") (pintype "bidirectional"))
      (node (ref "U$9") (pin "2") (pinfunction "2_2") (pintype "passive"))
    )
    (net (code "2") (name "+5V") (class "Default")
      (node (ref "D6") (pin "A") (pinfunction "A_A") (pintype "passive"))
      (node (ref "T3") (pin "3") (pinfunction "G_3") (pintype "passive"))
      (node (ref "U$8") (pin "T1") (pinfunction "T1_T1") (pintype "bidirectional"))
      (node (ref "U$8") (pin "T2") (pinfunction "T2_T2") (pintype "bidirectional"))
      (node (ref "U$8") (pin "T3") (pinfunction "T3_T3") (pintype "bidirectional"))
      (node (ref "U$8") (pin "T4") (pinfunction "T4_T4") (pintype "bidirectional"))
      (node (ref "U$8") (pin "T5") (pinfunction "T5_T5") (pintype "bidirectional"))
      (node (ref "U$8") (pin "T6") (pinfunction "T6_T6") (pintype "bidirectional"))
    )
    (net (code "3") (name "/ALT_CAMERA_SERVO_MOTOR_PWM") (class "Default")
      (node (ref "SV1") (pin "16") (pinfunction "16_16") (pintype "passive"))
      (node (ref "U$1") (pin "P96") (pinfunction "PB9_P96") (pintype "bidirectional"))
      (node (ref "U$8") (pin "T60") (pinfunction "T60_T60") (pintype "bidirectional"))
    )
    (net (code "4") (name "/BUS_SPEED") (class "Default")
      (node (ref "R22") (pin "2") (pinfunction "2_2") (pintype "passive"))
      (node (ref "U$4") (pin "2") (pinfunction "LED2/NINTSEL_2") (pintype "bidirectional"))
      (node (ref "U$7") (pin "10") (pinfunction "G_GND_10") (pintype "bidirectional"))
    )
    (net (code "5") (name "/CANH1") (class "Default")
      (node (ref "R5") (pin "2") (pinfunction "2_2") (pintype "passive"))
      (node (ref "U$6") (pin "7") (pinfunction "CANH_7") (pintype "bidirectional"))
      (node (ref "U$8") (pin "T39") (pinfunction "T39_T39") (pintype "bidirectional"))
    )
    (net (code "6") (name "/CANL1") (class "Default")
      (node (ref "R5") (pin "1") (pinfunction "1_1") (pintype "passive"))
      (node (ref "U$6") (pin "6") (pinfunction "CANL_6") (pintype "bidirectional"))
      (node (ref "U$8") (pin "T38") (pinfunction "T38_T38") (pintype "bidirectional"))
    )
    (net (code "7") (name "/CAN_RX") (class "Default")
      (node (ref "SV1") (pin "12") (pinfunction "12_12") (pintype "passive"))
      (node (ref "U$1") (pin "P91") (pinfunction "PB5_P91") (pintype "bidirectional"))
      (node (ref "U$6") (pin "4") (pinfunction "RXD_4") (pintype "bidirectional"))
    )
    (net (code "8") (name "/CAN_TX") (class "Default")
      (node (ref "SV1") (pin "13") (pinfunction "13_13") (pintype "passive"))
      (node (ref "U$1") (pin "P92") (pinfunction "PB6_P92") (pintype "bidirectional"))
      (node (ref "U$6") (pin "1") (pinfunction "TXD_1") (pintype "bidirectional"))
    )
    (net (code "9") (name "/CRS_DV") (class "Default")
      (node (ref "RN1") (pin "3") (pinfunction "1_3") (pintype "passive"))
      (node (ref "SV5") (pin "7") (pinfunction "7_7") (pintype "passive"))
      (node (ref "U$1") (pin "P32") (pinfunction "PA7_P32") (pintype "bidirectional"))
    )
    (net (code "10") (name "/DIFF_RD+") (class "Default")
      (node (ref "R16") (pin "1") (pinfunction "1_1") (pintype "passive"))
      (node (ref "U$4") (pin "23") (pinfunction "RXP_23") (pintype "bidirectional"))
      (node (ref "U$7") (pin "3") (pinfunction "RD+_3") (pintype "bidirectional"))
    )
    (net (code "11") (name "/DIFF_RD-") (class "Default")
      (node (ref "R17") (pin "1") (pinfunction "1_1") (pintype "passive"))
      (node (ref "U$4") (pin "22") (pinfunction "RXN_22") (pintype "bidirectional"))
      (node (ref "U$7") (pin "6") (pinfunction "RD-_6") (pintype "bidirectional"))
    )
    (net (code "12") (name "/DIFF_TD+") (class "Default")
      (node (ref "R19") (pin "1") (pinfunction "1_1") (pintype "passive"))
      (node (ref "U$4") (pin "21") (pinfunction "TXP_21") (pintype "bidirectional"))
      (node (ref "U$7") (pin "1") (pinfunction "TD+_1") (pintype "bidirectional"))
    )
    (net (code "13") (name "/DIFF_TD-") (class "Default")
      (node (ref "R18") (pin "1") (pinfunction "1_1") (pintype "passive"))
      (node (ref "U$4") (pin "20") (pinfunction "TXN_20") (pintype "bidirectional"))
      (node (ref "U$7") (pin "2") (pinfunction "TD-_2") (pintype "bidirectional"))
    )
    (net (code "14") (name "/I2C1_SCL") (class "Default")
      (node (ref "R9") (pin "1") (pinfunction "1_1") (pintype "passive"))
      (node (ref "SV1") (pin "15") (pinfunction "15_15") (pintype "passive"))
      (node (ref "U$1") (pin "P95") (pinfunction "PB8_P95") (pintype "bidirectional"))
      (node (ref "U$8") (pin "T42") (pinfunction "T42_T42") (pintype "bidirectional"))
    )
    (net (code "15") (name "/I2C1_SDA") (class "Default")
      (node (ref "R10") (pin "1") (pinfunction "1_1") (pintype "passive"))
      (node (ref "SV1") (pin "14") (pinfunction "14_14") (pintype "passive"))
      (node (ref "U$1") (pin "P93") (pinfunction "PB7_P93") (pintype "bidirectional"))
      (node (ref "U$8") (pin "T41") (pinfunction "T41_T41") (pintype "bidirectional"))
    )
    (net (code "16") (name "/I2C3_SCL") (class "Default")
      (node (ref "R3") (pin "1") (pinfunction "1_1") (pintype "passive"))
      (node (ref "SV2") (pin "12") (pinfunction "12_12") (pintype "passive"))
      (node (ref "U$1") (pin "P67") (pinfunction "PA8_P67") (pintype "bidirectional"))
      (node (ref "U$8") (pin "B36") (pinfunction "B36_B36") (pintype "bidirectional"))
    )
    (net (code "17") (name "/I2C3_SDA") (class "Default")
      (node (ref "R4") (pin "1") (pinfunction "1_1") (pintype "passive"))
      (node (ref "SV2") (pin "11") (pinfunction "11_11") (pintype "passive"))
      (node (ref "U$1") (pin "P66") (pinfunction "PC9_P66") (pintype "bidirectional"))
      (node (ref "U$8") (pin "B35") (pinfunction "B35_B35") (pintype "bidirectional"))
    )
    (net (code "18") (name "/LINK{slash}ACT") (class "Default")
      (node (ref "U$4") (pin "3") (pinfunction "LED1/REGOFF_3") (pintype "bidirectional"))
      (node (ref "U$7") (pin "12") (pinfunction "Y_12") (pintype "bidirectional"))
    )
    (net (code "19") (name "/MAIN_CAMERA_SERVO_MOTOR_PWM") (class "Default")
      (node (ref "SV1") (pin "11") (pinfunction "11_11") (pintype "passive"))
      (node (ref "U$1") (pin "P90") (pinfunction "PB4_P90") (pintype "bidirectional"))
      (node (ref "U$8") (pin "T37") (pinfunction "T37_T37") (pintype "bidirectional"))
    )
    (net (code "20") (name "/MDC") (class "Default")
      (node (ref "RN4") (pin "8") (pinfunction "2_8") (pintype "passive"))
      (node (ref "SV5") (pin "5") (pinfunction "5_5") (pintype "passive"))
      (node (ref "U$1") (pin "P16") (pinfunction "PC1_P16") (pintype "bidirectional"))
    )
    (net (code "21") (name "/MDIO") (class "Default")
      (node (ref "RN4") (pin "7") (pinfunction "2_7") (pintype "passive"))
      (node (ref "SV5") (pin "6") (pinfunction "6_6") (pintype "passive"))
      (node (ref "U$1") (pin "P25") (pinfunction "PA2_P25") (pintype "bidirectional"))
    )
    (net (code "22") (name "/NRST") (class "Default")
      (node (ref "R8") (pin "1") (pinfunction "1_1") (pintype "passive"))
      (node (ref "U$4") (pin "15") (pinfunction "NRST_15") (pintype "bidirectional"))
    )
    (net (code "23") (name "/OSC_IN") (class "Default")
      (node (ref "Q1") (pin "3") (pinfunction "FO_3") (pintype "output"))
      (node (ref "SV3") (pin "3") (pinfunction "3_3") (pintype "passive"))
      (node (ref "U$1") (pin "P12") (pinfunction "PH0_P12") (pintype "bidirectional"))
    )
    (net (code "24") (name "/PA0") (class "Default")
      (node (ref "U$1") (pin "P23") (pinfunction "PA0_P23") (pintype "bidirectional"))
    )
    (net (code "25") (name "/PA3") (class "Default")
      (node (ref "U$1") (pin "P26") (pinfunction "PA3_P26") (pintype "bidirectional"))
    )
    (net (code "26") (name "/PA5") (class "Default")
      (node (ref "U$1") (pin "P30") (pinfunction "PA5_P30") (pintype "bidirectional"))
    )
    (net (code "27") (name "/PA6") (class "Default")
      (node (ref "U$1") (pin "P31") (pinfunction "PA6_P31") (pintype "bidirectional"))
    )
    (net (code "28") (name "/PA9") (class "Default")
      (node (ref "SV2") (pin "13") (pinfunction "13_13") (pintype "passive"))
      (node (ref "U$1") (pin "P68") (pinfunction "PA9_P68") (pintype "bidirectional"))
    )
    (net (code "29") (name "/PA10") (class "Default")
      (node (ref "SV2") (pin "14") (pinfunction "14_14") (pintype "passive"))
      (node (ref "U$1") (pin "P69") (pinfunction "PA10_P69") (pintype "bidirectional"))
    )
    (net (code "30") (name "/PA13") (class "Default")
      (node (ref "U$1") (pin "P72") (pinfunction "PA13_P72") (pintype "bidirectional"))
    )
    (net (code "31") (name "/PA14") (class "Default")
      (node (ref "U$1") (pin "P76") (pinfunction "PA14_P76") (pintype "bidirectional"))
    )
    (net (code "32") (name "/PA15") (class "Default")
      (node (ref "U$1") (pin "P77") (pinfunction "PA15_P77") (pintype "bidirectional"))
    )
    (net (code "33") (name "/PB0") (class "Default")
      (node (ref "U$1") (pin "P35") (pinfunction "PB0_P35") (pintype "bidirectional"))
    )
    (net (code "34") (name "/PB1") (class "Default")
      (node (ref "U$1") (pin "P36") (pinfunction "PB1_P36") (pintype "bidirectional"))
    )
    (net (code "35") (name "/PB2") (class "Default")
      (node (ref "U$1") (pin "P37") (pinfunction "PB2_P37") (pintype "bidirectional"))
    )
    (net (code "36") (name "/PB10") (class "Default")
      (node (ref "U$1") (pin "P47") (pinfunction "PB10_P47") (pintype "bidirectional"))
    )
    (net (code "37") (name "/PB14") (class "Default")
      (node (ref "U$1") (pin "P53") (pinfunction "PB14_P53") (pintype "bidirectional"))
    )
    (net (code "38") (name "/PB15") (class "Default")
      (node (ref "U$1") (pin "P54") (pinfunction "PB15_P54") (pintype "bidirectional"))
    )
    (net (code "39") (name "/PC0") (class "Default")
      (node (ref "U$1") (pin "P15") (pinfunction "PC0_P15") (pintype "bidirectional"))
    )
    (net (code "40") (name "/PC2") (class "Default")
      (node (ref "U$1") (pin "P17") (pinfunction "PC2_P17") (pintype "bidirectional"))
    )
    (net (code "41") (name "/PC3") (class "Default")
      (node (ref "U$1") (pin "P18") (pinfunction "PC3_P18") (pintype "bidirectional"))
    )
    (net (code "42") (name "/PC6") (class "Default")
      (node (ref "SV2") (pin "8") (pinfunction "8_8") (pintype "passive"))
      (node (ref "U$1") (pin "P63") (pinfunction "PC6_P63") (pintype "bidirectional"))
    )
    (net (code "43") (name "/PC7") (class "Default")
      (node (ref "SV2") (pin "9") (pinfunction "9_9") (pintype "passive"))
      (node (ref "U$1") (pin "P64") (pinfunction "PC7_P64") (pintype "bidirectional"))
    )
    (net (code "44") (name "/PC8") (class "Default")
      (node (ref "SV2") (pin "10") (pinfunction "10_10") (pintype "passive"))
      (node (ref "U$1") (pin "P65") (pinfunction "PC8_P65") (pintype "bidirectional"))
    )
    (net (code "45") (name "/PC10") (class "Default")
      (node (ref "SV1") (pin "1") (pinfunction "1_1") (pintype "passive"))
      (node (ref "U$1") (pin "P78") (pinfunction "PC10_P78") (pintype "bidirectional"))
    )
    (net (code "46") (name "/PC12") (class "Default")
      (node (ref "SV1") (pin "3") (pinfunction "3_3") (pintype "passive"))
      (node (ref "U$1") (pin "P80") (pinfunction "PC12_P80") (pintype "bidirectional"))
    )
    (net (code "47") (name "/PC13") (class "Default")
      (node (ref "SV3") (pin "6") (pinfunction "6_6") (pintype "passive"))
      (node (ref "U$1") (pin "P7") (pinfunction "PC13_P7") (pintype "bidirectional"))
    )
    (net (code "48") (name "/PC14") (class "Default")
      (node (ref "SV3") (pin "5") (pinfunction "5_5") (pintype "passive"))
      (node (ref "U$1") (pin "P8") (pinfunction "PC14_P8") (pintype "bidirectional"))
    )
    (net (code "49") (name "/PC15") (class "Default")
      (node (ref "SV3") (pin "4") (pinfunction "4_4") (pintype "passive"))
      (node (ref "U$1") (pin "P9") (pinfunction "PC15_P9") (pintype "bidirectional"))
    )
    (net (code "50") (name "/PD0") (class "Default")
      (node (ref "SV1") (pin "4") (pinfunction "4_4") (pintype "passive"))
      (node (ref "U$1") (pin "P81") (pinfunction "PD0_P81") (pintype "bidirectional"))
    )
    (net (code "51") (name "/PD1") (class "Default")
      (node (ref "SV1") (pin "5") (pinfunction "5_5") (pintype "passive"))
      (node (ref "U$1") (pin "P82") (pinfunction "PD1_P82") (pintype "bidirectional"))
    )
    (net (code "52") (name "/PD2") (class "Default")
      (node (ref "SV1") (pin "6") (pinfunction "6_6") (pintype "passive"))
      (node (ref "U$1") (pin "P83") (pinfunction "PD2_P83") (pintype "bidirectional"))
    )
    (net (code "53") (name "/PD6") (class "Default")
      (node (ref "U$1") (pin "P87") (pinfunction "PD6_P87") (pintype "bidirectional"))
    )
    (net (code "54") (name "/PD7") (class "Default")
      (node (ref "U$1") (pin "P88") (pinfunction "PD7_P88") (pintype "bidirectional"))
    )
    (net (code "55") (name "/PD8") (class "Default")
      (node (ref "SV2") (pin "1") (pinfunction "1_1") (pintype "passive"))
      (node (ref "U$1") (pin "P55") (pinfunction "PD8_P55") (pintype "bidirectional"))
    )
    (net (code "56") (name "/PD9") (class "Default")
      (node (ref "SV2") (pin "2") (pinfunction "2_2") (pintype "passive"))
      (node (ref "U$1") (pin "P56") (pinfunction "PD9_P56") (pintype "bidirectional"))
    )
    (net (code "57") (name "/PD10") (class "Default")
      (node (ref "U$1") (pin "P57") (pinfunction "PD10_P57") (pintype "bidirectional"))
    )
    (net (code "58") (name "/PD11") (class "Default")
      (node (ref "R11") (pin "2") (pinfunction "2_2") (pintype "passive"))
      (node (ref "SV2") (pin "3") (pinfunction "3_3") (pintype "passive"))
      (node (ref "U$1") (pin "P58") (pinfunction "PD11_P58") (pintype "bidirectional"))
    )
    (net (code "59") (name "/PD12") (class "Default")
      (node (ref "R12") (pin "2") (pinfunction "2_2") (pintype "passive"))
      (node (ref "SV2") (pin "4") (pinfunction "4_4") (pintype "passive"))
      (node (ref "U$1") (pin "P59") (pinfunction "PD12_P59") (pintype "bidirectional"))
    )
    (net (code "60") (name "/PD13") (class "Default")
      (node (ref "R13") (pin "2") (pinfunction "2_2") (pintype "passive"))
      (node (ref "SV2") (pin "5") (pinfunction "5_5") (pintype "passive"))
      (node (ref "U$1") (pin "P60") (pinfunction "PD13_P60") (pintype "bidirectional"))
    )
    (net (code "61") (name "/PD14") (class "Default")
      (node (ref "R14") (pin "2") (pinfunction "2_2") (pintype "passive"))
      (node (ref "SV2") (pin "6") (pinfunction "6_6") (pintype "passive"))
      (node (ref "U$1") (pin "P61") (pinfunction "PD14_P61") (pintype "bidirectional"))
    )
    (net (code "62") (name "/PD15") (class "Default")
      (node (ref "SV2") (pin "7") (pinfunction "7_7") (pintype "passive"))
      (node (ref "U$1") (pin "P62") (pinfunction "PD15_P62") (pintype "bidirectional"))
    )
    (net (code "63") (name "/PE0") (class "Default")
      (node (ref "U$1") (pin "P97") (pinfunction "PE0_P97") (pintype "bidirectional"))
    )
    (net (code "64") (name "/PE1") (class "Default")
      (node (ref "U$1") (pin "P98") (pinfunction "PE1_P98") (pintype "bidirectional"))
    )
    (net (code "65") (name "/PE2") (class "Default")
      (node (ref "SV3") (pin "16") (pinfunction "16_16") (pintype "passive"))
      (node (ref "U$1") (pin "P1") (pinfunction "PE2_P1") (pintype "bidirectional"))
    )
    (net (code "66") (name "/PE3") (class "Default")
      (node (ref "SV3") (pin "15") (pinfunction "15_15") (pintype "passive"))
      (node (ref "U$1") (pin "P2") (pinfunction "PE3_P2") (pintype "bidirectional"))
    )
    (net (code "67") (name "/PE4") (class "Default")
      (node (ref "SV3") (pin "14") (pinfunction "14_14") (pintype "passive"))
      (node (ref "U$1") (pin "P3") (pinfunction "PE4_P3") (pintype "bidirectional"))
    )
    (net (code "68") (name "/PE5") (class "Default")
      (node (ref "SV3") (pin "13") (pinfunction "13_13") (pintype "passive"))
      (node (ref "U$1") (pin "P4") (pinfunction "PE5_P4") (pintype "bidirectional"))
    )
    (net (code "69") (name "/PE6") (class "Default")
      (node (ref "SV3") (pin "12") (pinfunction "12_12") (pintype "passive"))
      (node (ref "U$1") (pin "P5") (pinfunction "PE6_P5") (pintype "bidirectional"))
    )
    (net (code "70") (name "/PE7") (class "Default")
      (node (ref "U$1") (pin "P38") (pinfunction "PE7_P38") (pintype "bidirectional"))
    )
    (net (code "71") (name "/PE8") (class "Default")
      (node (ref "U$1") (pin "P39") (pinfunction "PE8_P39") (pintype "bidirectional"))
    )
    (net (code "72") (name "/PE9") (class "Default")
      (node (ref "U$1") (pin "P40") (pinfunction "PE9_P40") (pintype "bidirectional"))
    )
    (net (code "73") (name "/PE10") (class "Default")
      (node (ref "U$1") (pin "P41") (pinfunction "PE10_P41") (pintype "bidirectional"))
    )
    (net (code "74") (name "/PE11") (class "Default")
      (node (ref "U$1") (pin "P42") (pinfunction "PE11_P42") (pintype "bidirectional"))
    )
    (net (code "75") (name "/PE12") (class "Default")
      (node (ref "U$1") (pin "P43") (pinfunction "PE12_P43") (pintype "bidirectional"))
    )
    (net (code "76") (name "/PE13") (class "Default")
      (node (ref "U$1") (pin "P44") (pinfunction "PE13_P44") (pintype "bidirectional"))
    )
    (net (code "77") (name "/PE14") (class "Default")
      (node (ref "U$1") (pin "P45") (pinfunction "PE14_P45") (pintype "bidirectional"))
    )
    (net (code "78") (name "/PE15") (class "Default")
      (node (ref "U$1") (pin "P46") (pinfunction "PE15_P46") (pintype "bidirectional"))
    )
    (net (code "79") (name "/PH1") (class "Default")
      (node (ref "SV3") (pin "2") (pinfunction "2_2") (pintype "passive"))
      (node (ref "U$1") (pin "P13") (pinfunction "PH1_P13") (pintype "bidirectional"))
    )
    (net (code "80") (name "/REFCLK") (class "Default")
      (node (ref "RN3") (pin "5") (pinfunction "2_5") (pintype "passive"))
      (node (ref "SV5") (pin "8") (pinfunction "8_8") (pintype "passive"))
      (node (ref "U$1") (pin "P24") (pinfunction "PA1_P24") (pintype "bidirectional"))
    )
    (net (code "81") (name "/RXD0") (class "Default")
      (node (ref "RN1") (pin "2") (pinfunction "1_2") (pintype "passive"))
      (node (ref "SV5") (pin "10") (pinfunction "10_10") (pintype "passive"))
      (node (ref "U$1") (pin "P33") (pinfunction "PC4_P33") (pintype "bidirectional"))
    )
    (net (code "82") (name "/RXD1") (class "Default")
      (node (ref "RN1") (pin "1") (pinfunction "1_1") (pintype "passive"))
      (node (ref "SV5") (pin "9") (pinfunction "9_9") (pintype "passive"))
      (node (ref "U$1") (pin "P34") (pinfunction "PC5_P34") (pintype "bidirectional"))
    )
    (net (code "83") (name "/RXERR") (class "Default")
      (node (ref "U$4") (pin "10") (pinfunction "RXER/PHYAD0_10") (pintype "bidirectional"))
    )
    (net (code "84") (name "/SHIFTREG_CLK") (class "Default")
      (node (ref "SV1") (pin "8") (pinfunction "8_8") (pintype "passive"))
      (node (ref "U$1") (pin "P85") (pinfunction "PD4_P85") (pintype "bidirectional"))
      (node (ref "U$8") (pin "T32") (pinfunction "T32_T32") (pintype "bidirectional"))
    )
    (net (code "85") (name "/SHIFTREG_DATA") (class "Default")
      (node (ref "SV1") (pin "9") (pinfunction "9_9") (pintype "passive"))
      (node (ref "U$1") (pin "P86") (pinfunction "PD5_P86") (pintype "bidirectional"))
      (node (ref "U$8") (pin "T33") (pinfunction "T33_T33") (pintype "bidirectional"))
    )
    (net (code "86") (name "/SHIFTREG_ENABLE") (class "Default")
      (node (ref "SV1") (pin "7") (pinfunction "7_7") (pintype "passive"))
      (node (ref "U$1") (pin "P84") (pinfunction "PD3_P84") (pintype "bidirectional"))
      (node (ref "U$8") (pin "T31") (pinfunction "T31_T31") (pintype "bidirectional"))
    )
    (net (code "87") (name "/SONAR_DAC") (class "Default")
      (node (ref "U$1") (pin "P29") (pinfunction "PA4_P29") (pintype "bidirectional"))
      (node (ref "U$8") (pin "B46") (pinfunction "B46_B46") (pintype "bidirectional"))
    )
    (net (code "88") (name "/SONAR_PWM") (class "Default")
      (node (ref "SV1") (pin "10") (pinfunction "10_10") (pintype "passive"))
      (node (ref "U$1") (pin "P89") (pinfunction "PB3_P89") (pintype "bidirectional"))
      (node (ref "U$8") (pin "T34") (pinfunction "T34_T34") (pintype "bidirectional"))
    )
    (net (code "89") (name "/TEMP_BACKUP") (class "Default")
      (node (ref "SV1") (pin "2") (pinfunction "2_2") (pintype "passive"))
      (node (ref "U$1") (pin "P79") (pinfunction "PC11_P79") (pintype "bidirectional"))
      (node (ref "U$8") (pin "T25") (pinfunction "T25_T25") (pintype "bidirectional"))
    )
    (net (code "90") (name "/TXD0") (class "Default")
      (node (ref "RN3") (pin "7") (pinfunction "2_7") (pintype "passive"))
      (node (ref "SV5") (pin "11") (pinfunction "11_11") (pintype "passive"))
      (node (ref "U$1") (pin "P51") (pinfunction "PB12_P51") (pintype "bidirectional"))
    )
    (net (code "91") (name "/TXD1") (class "Default")
      (node (ref "RN3") (pin "8") (pinfunction "2_8") (pintype "passive"))
      (node (ref "SV5") (pin "14") (pinfunction "14_14") (pintype "passive"))
      (node (ref "U$1") (pin "P52") (pinfunction "PB13_P52") (pintype "bidirectional"))
    )
    (net (code "92") (name "/TXEN") (class "Default")
      (node (ref "RN3") (pin "6") (pinfunction "2_6") (pintype "passive"))
      (node (ref "SV5") (pin "12") (pinfunction "12_12") (pintype "passive"))
      (node (ref "U$1") (pin "P48") (pinfunction "PB11_P48") (pintype "bidirectional"))
    )
    (net (code "93") (name "/USB_D+") (class "Default")
      (node (ref "RN2") (pin "3") (pinfunction "2_3") (pintype "passive"))
      (node (ref "U$1") (pin "P71") (pinfunction "PA12_P71") (pintype "bidirectional"))
    )
    (net (code "94") (name "/USB_D-") (class "Default")
      (node (ref "RN2") (pin "4") (pinfunction "2_4") (pintype "passive"))
      (node (ref "U$1") (pin "P70") (pinfunction "PA11_P70") (pintype "bidirectional"))
    )
    (net (code "95") (name "/XTAL1") (class "Default")
      (node (ref "Q2") (pin "3") (pinfunction "FO_3") (pintype "output"))
      (node (ref "U$4") (pin "5") (pinfunction "XTAL1/CLKIN_5") (pintype "bidirectional"))
    )
    (net (code "96") (name "/XTAL2") (class "Default")
      (node (ref "U$4") (pin "4") (pinfunction "XTAL2_4") (pintype "bidirectional"))
    )
    (net (code "97") (name "GND") (class "Default")
      (node (ref "C1") (pin "2") (pinfunction "2_2") (pintype "passive"))
      (node (ref "C10") (pin "2") (pinfunction "2_2") (pintype "passive"))
      (node (ref "C11") (pin "2") (pinfunction "2_2") (pintype "passive"))
      (node (ref "C12") (pin "2") (pinfunction "2_2") (pintype "passive"))
      (node (ref "C13") (pin "2") (pinfunction "2_2") (pintype "passive"))
      (node (ref "C14") (pin "2") (pinfunction "2_2") (pintype "passive"))
      (node (ref "C15") (pin "1") (pinfunction "1_1") (pintype "passive"))
      (node (ref "C16") (pin "1") (pinfunction "1_1") (pintype "passive"))
      (node (ref "C17") (pin "2") (pinfunction "2_2") (pintype "passive"))
      (node (ref "C18") (pin "2") (pinfunction "2_2") (pintype "passive"))
      (node (ref "C19") (pin "1") (pinfunction "1_1") (pintype "passive"))
      (node (ref "C2") (pin "2") (pinfunction "2_2") (pintype "passive"))
      (node (ref "C20") (pin "1") (pinfunction "1_1") (pintype "passive"))
      (node (ref "C21") (pin "1") (pinfunction "1_1") (pintype "passive"))
      (node (ref "C22") (pin "2") (pinfunction "2_2") (pintype "passive"))
      (node (ref "C3") (pin "2") (pinfunction "2_2") (pintype "passive"))
      (node (ref "C4") (pin "2") (pinfunction "2_2") (pintype "passive"))
      (node (ref "C6") (pin "2") (pinfunction "2_2") (pintype "passive"))
      (node (ref "C8") (pin "2") (pinfunction "2_2") (pintype "passive"))
      (node (ref "C9") (pin "2") (pinfunction "2_2") (pintype "passive"))
      (node (ref "D2") (pin "C") (pinfunction "C_C") (pintype "passive"))
      (node (ref "D3") (pin "C") (pinfunction "C_C") (pintype "passive"))
      (node (ref "D4") (pin "C") (pinfunction "C_C") (pintype "passive"))
      (node (ref "D5") (pin "C") (pinfunction "C_C") (pintype "passive"))
      (node (ref "Q1") (pin "2") (pinfunction "GND_2") (pintype "power_in"))
      (node (ref "Q2") (pin "2") (pinfunction "GND_2") (pintype "power_in"))
      (node (ref "R1") (pin "1") (pinfunction "1_1") (pintype "passive"))
      (node (ref "R21") (pin "1") (pinfunction "1_1") (pintype "passive"))
      (node (ref "R22") (pin "1") (pinfunction "1_1") (pintype "passive"))
      (node (ref "R6") (pin "1") (pinfunction "1_1") (pintype "passive"))
      (node (ref "SV2") (pin "15") (pinfunction "15_15") (pintype "passive"))
      (node (ref "SV3") (pin "1") (pinfunction "1_1") (pintype "passive"))
      (node (ref "SV3") (pin "11") (pinfunction "11_11") (pintype "passive"))
      (node (ref "SV3") (pin "7") (pinfunction "7_7") (pintype "passive"))
      (node (ref "SV3") (pin "9") (pinfunction "9_9") (pintype "passive"))
      (node (ref "SV5") (pin "3") (pinfunction "3_3") (pintype "passive"))
      (node (ref "SV5") (pin "4") (pinfunction "4_4") (pintype "passive"))
      (node (ref "T4") (pin "GND") (pinfunction "GND_GND") (pintype "bidirectional"))
      (node (ref "U$1") (pin "P10") (pinfunction "VSS1_P10") (pintype "bidirectional"))
      (node (ref "U$1") (pin "P20") (pinfunction "VSSA_P20") (pintype "bidirectional"))
      (node (ref "U$1") (pin "P27") (pinfunction "VSS2_P27") (pintype "bidirectional"))
      (node (ref "U$1") (pin "P74") (pinfunction "VSS3_P74") (pintype "bidirectional"))
      (node (ref "U$1") (pin "P99") (pinfunction "VSS4_P99") (pintype "bidirectional"))
      (node (ref "U$2") (pin "1") (pinfunction "P$1_1") (pintype "bidirectional"))
      (node (ref "U$4") (pin "VSS_PAD") (pinfunction "VSS_PAD_VSS_PAD") (pintype "bidirectional"))
      (node (ref "U$5") (pin "GND1") (pinfunction "GND_GND1") (pintype "bidirectional"))
      (node (ref "U$5") (pin "GND2") (pinfunction "GND_GND2") (pintype "bidirectional"))
      (node (ref "U$5") (pin "GND3") (pinfunction "GND_GND3") (pintype "bidirectional"))
      (node (ref "U$5") (pin "GND4") (pinfunction "GND_GND4") (pintype "bidirectional"))
      (node (ref "U$5") (pin "GND7") (pinfunction "GND_GND7") (pintype "bidirectional"))
      (node (ref "U$5") (pin "GND8") (pinfunction "GND_GND8") (pintype "bidirectional"))
      (node (ref "U$5") (pin "P4") (pinfunction "ID_P4") (pintype "bidirectional"))
      (node (ref "U$5") (pin "P5") (pinfunction "GND_P5") (pintype "bidirectional"))
      (node (ref "U$6") (pin "2") (pinfunction "GND_2") (pintype "bidirectional"))
      (node (ref "U$7") (pin "15") (pinfunction "CHS1_15") (pintype "bidirectional"))
      (node (ref "U$7") (pin "16") (pinfunction "CHS2_16") (pintype "bidirectional"))
      (node (ref "U$7") (pin "8") (pinfunction "GND_8") (pintype "bidirectional"))
      (node (ref "U$8") (pin "T11") (pinfunction "T11_T11") (pintype "bidirectional"))
      (node (ref "U$8") (pin "T12") (pinfunction "T12_T12") (pintype "bidirectional"))
      (node (ref "U$8") (pin "T13") (pinfunction "T13_T13") (pintype "bidirectional"))
      (node (ref "U$8") (pin "T14") (pinfunction "T14_T14") (pintype "bidirectional"))
      (node (ref "U$8") (pin "T15") (pinfunction "T15_T15") (pintype "bidirectional"))
      (node (ref "U$8") (pin "T16") (pinfunction "T16_T16") (pintype "bidirectional"))
      (node (ref "U$8") (pin "T17") (pinfunction "T17_T17") (pintype "bidirectional"))
      (node (ref "U$8") (pin "T18") (pinfunction "T18_T18") (pintype "bidirectional"))
    )
    (net (code "98") (name "Net-(D2-PadA)") (class "Default")
      (node (ref "D2") (pin "A") (pinfunction "A_A") (pintype "passive"))
      (node (ref "R11") (pin "1") (pinfunction "1_1") (pintype "passive"))
    )
    (net (code "99") (name "Net-(D3-PadA)") (class "Default")
      (node (ref "D3") (pin "A") (pinfunction "A_A") (pintype "passive"))
      (node (ref "R12") (pin "1") (pinfunction "1_1") (pintype "passive"))
    )
    (net (code "100") (name "Net-(D4-PadA)") (class "Default")
      (node (ref "D4") (pin "A") (pinfunction "A_A") (pintype "passive"))
      (node (ref "R13") (pin "1") (pinfunction "1_1") (pintype "passive"))
    )
    (net (code "101") (name "Net-(D5-PadA)") (class "Default")
      (node (ref "D5") (pin "A") (pinfunction "A_A") (pintype "passive"))
      (node (ref "R14") (pin "1") (pinfunction "1_1") (pintype "passive"))
    )
    (net (code "102") (name "Net-(RN1A-2)") (class "Default")
      (node (ref "RN1") (pin "8") (pinfunction "2_8") (pintype "passive"))
      (node (ref "U$4") (pin "7") (pinfunction "RXD1/MODE1_7") (pintype "bidirectional"))
    )
    (net (code "103") (name "Net-(RN1B-2)") (class "Default")
      (node (ref "RN1") (pin "7") (pinfunction "2_7") (pintype "passive"))
      (node (ref "U$4") (pin "8") (pinfunction "RXD0/MODE0_8") (pintype "bidirectional"))
    )
    (net (code "104") (name "Net-(RN1C-2)") (class "Default")
      (node (ref "RN1") (pin "6") (pinfunction "2_6") (pintype "passive"))
      (node (ref "U$4") (pin "11") (pinfunction "CRS_DV/MODE2_11") (pintype "bidirectional"))
    )
    (net (code "105") (name "Net-(RN2B-1)") (class "Default")
      (node (ref "RN2") (pin "2") (pinfunction "1_2") (pintype "passive"))
      (node (ref "U$5") (pin "P3") (pinfunction "D+_P3") (pintype "bidirectional"))
    )
    (net (code "106") (name "Net-(RN3B-1)") (class "Default")
      (node (ref "RN3") (pin "2") (pinfunction "1_2") (pintype "passive"))
      (node (ref "U$4") (pin "17") (pinfunction "TXD0_17") (pintype "bidirectional"))
    )
    (net (code "107") (name "Net-(RN3C-1)") (class "Default")
      (node (ref "RN3") (pin "3") (pinfunction "1_3") (pintype "passive"))
      (node (ref "U$4") (pin "16") (pinfunction "TXEN_16") (pintype "bidirectional"))
    )
    (net (code "108") (name "Net-(RN3D-1)") (class "Default")
      (node (ref "RN3") (pin "4") (pinfunction "1_4") (pintype "passive"))
      (node (ref "U$4") (pin "14") (pinfunction "NINT/REFCLKO_14") (pintype "bidirectional"))
    )
    (net (code "109") (name "Net-(RN4B-1)") (class "Default")
      (node (ref "R23") (pin "1") (pinfunction "1_1") (pintype "passive"))
      (node (ref "RN4") (pin "2") (pinfunction "1_2") (pintype "passive"))
      (node (ref "U$4") (pin "12") (pinfunction "MDIO_12") (pintype "bidirectional"))
    )
    (net (code "110") (name "Net-(T3-D)") (class "Default")
      (node (ref "T3") (pin "1") (pinfunction "D_1") (pintype "passive"))
      (node (ref "U$5") (pin "P1") (pinfunction "VCC_P1") (pintype "bidirectional"))
    )
    (net (code "111") (name "Net-(T3-S)") (class "Default")
      (node (ref "C12") (pin "1") (pinfunction "1_1") (pintype "passive"))
      (node (ref "D6") (pin "C") (pinfunction "C_C") (pintype "passive"))
      (node (ref "T3") (pin "2") (pinfunction "S_2") (pintype "passive"))
      (node (ref "T4") (pin "VIN") (pinfunction "VIN_VIN") (pintype "input"))
    )
    (net (code "112") (name "Net-(U$1F-BOOT0)") (class "Default")
      (node (ref "R1") (pin "2") (pinfunction "2_2") (pintype "passive"))
      (node (ref "U$1") (pin "P94") (pinfunction "BOOT0_P94") (pintype "bidirectional"))
      (node (ref "U$3") (pin "2") (pinfunction "P$2_2") (pintype "bidirectional"))
    )
    (net (code "113") (name "Net-(U$1F-NRST)") (class "Default")
      (node (ref "R2") (pin "1") (pinfunction "1_1") (pintype "passive"))
      (node (ref "U$1") (pin "P14") (pinfunction "NRST_P14") (pintype "bidirectional"))
      (node (ref "U$2") (pin "2") (pinfunction "P$2_2") (pintype "bidirectional"))
    )
    (net (code "114") (name "Net-(U$1F-VCAP_1)") (class "Default")
      (node (ref "C3") (pin "1") (pinfunction "1_1") (pintype "passive"))
      (node (ref "U$1") (pin "P49") (pinfunction "VCAP_1_P49") (pintype "bidirectional"))
    )
    (net (code "115") (name "Net-(U$1F-VCAP_2)") (class "Default")
      (node (ref "C2") (pin "1") (pinfunction "1_1") (pintype "passive"))
      (node (ref "U$1") (pin "P73") (pinfunction "VCAP_2_P73") (pintype "bidirectional"))
    )
    (net (code "116") (name "Net-(U$4-MDC)") (class "Default")
      (node (ref "RN4") (pin "1") (pinfunction "1_1") (pintype "passive"))
      (node (ref "U$4") (pin "13") (pinfunction "MDC_13") (pintype "bidirectional"))
    )
    (net (code "117") (name "Net-(U$4-RBIAS)") (class "Default")
      (node (ref "R21") (pin "2") (pinfunction "2_2") (pintype "passive"))
      (node (ref "U$4") (pin "24") (pinfunction "RBIAS_24") (pintype "bidirectional"))
    )
    (net (code "118") (name "Net-(U$4-TXD1)") (class "Default")
      (node (ref "RN3") (pin "1") (pinfunction "1_1") (pintype "passive"))
      (node (ref "U$4") (pin "18") (pinfunction "TXD1_18") (pintype "bidirectional"))
    )
    (net (code "119") (name "Net-(U$4-VDD1A)") (class "Default")
      (node (ref "U$4") (pin "1") (pinfunction "VDD2A_1") (pintype "bidirectional"))
      (node (ref "U$4") (pin "19") (pinfunction "VDD1A_19") (pintype "bidirectional"))
      (node (ref "U$9") (pin "1") (pinfunction "1_1") (pintype "passive"))
    )
    (net (code "120") (name "Net-(U$4-VDDCR)") (class "Default")
      (node (ref "C15") (pin "2") (pinfunction "2_2") (pintype "passive"))
      (node (ref "C16") (pin "2") (pinfunction "2_2") (pintype "passive"))
      (node (ref "U$4") (pin "6") (pinfunction "VDDCR_6") (pintype "bidirectional"))
    )
    (net (code "121") (name "Net-(U$5-D-)") (class "Default")
      (node (ref "RN2") (pin "1") (pinfunction "1_1") (pintype "passive"))
      (node (ref "U$5") (pin "P2") (pinfunction "D-_P2") (pintype "bidirectional"))
    )
    (net (code "122") (name "Net-(U$6-RS)") (class "Default")
      (node (ref "R6") (pin "2") (pinfunction "2_2") (pintype "passive"))
      (node (ref "U$6") (pin "8") (pinfunction "RS_8") (pintype "bidirectional"))
    )
    (net (code "123") (name "Net-(U$7-G)") (class "Default")
      (node (ref "R7") (pin "2") (pinfunction "2_2") (pintype "passive"))
      (node (ref "U$7") (pin "9") (pinfunction "G_9") (pintype "bidirectional"))
    )
    (net (code "124") (name "Net-(U$7-Y_GND)") (class "Default")
      (node (ref "R15") (pin "2") (pinfunction "2_2") (pintype "passive"))
      (node (ref "U$7") (pin "11") (pinfunction "Y_GND_11") (pintype "bidirectional"))
    )
    (net (code "125") (name "unconnected-(Q1-OE-Pad1)") (class "Default")
      (node (ref "Q1") (pin "1") (pinfunction "OE_1") (pintype "input"))
    )
    (net (code "126") (name "unconnected-(Q2-OE-Pad1)") (class "Default")
      (node (ref "Q2") (pin "1") (pinfunction "OE_1") (pintype "input"))
    )
    (net (code "127") (name "unconnected-(SV5-Pad13)") (class "Default")
      (node (ref "SV5") (pin "13") (pinfunction "13_13") (pintype "passive"))
    )
    (net (code "128") (name "unconnected-(U$6-SHDN-Pad5)") (class "Default")
      (node (ref "U$6") (pin "5") (pinfunction "SHDN_5") (pintype "bidirectional"))
    )
    (net (code "129") (name "unconnected-(U$7-NC-Pad7)") (class "Default")
      (node (ref "U$7") (pin "7") (pinfunction "NC_7") (pintype "bidirectional"))
    )
    (net (code "130") (name "unconnected-(U$8-PadB1)") (class "Default")
      (node (ref "U$8") (pin "B1") (pinfunction "B1_B1") (pintype "bidirectional"))
    )
    (net (code "131") (name "unconnected-(U$8-PadB2)") (class "Default")
      (node (ref "U$8") (pin "B2") (pinfunction "B2_B2") (pintype "bidirectional"))
    )
    (net (code "132") (name "unconnected-(U$8-PadB3)") (class "Default")
      (node (ref "U$8") (pin "B3") (pinfunction "B3_B3") (pintype "bidirectional"))
    )
    (net (code "133") (name "unconnected-(U$8-PadB4)") (class "Default")
      (node (ref "U$8") (pin "B4") (pinfunction "B4_B4") (pintype "bidirectional"))
    )
    (net (code "134") (name "unconnected-(U$8-PadB5)") (class "Default")
      (node (ref "U$8") (pin "B5") (pinfunction "B5_B5") (pintype "bidirectional"))
    )
    (net (code "135") (name "unconnected-(U$8-PadB6)") (class "Default")
      (node (ref "U$8") (pin "B6") (pinfunction "B6_B6") (pintype "bidirectional"))
    )
    (net (code "136") (name "unconnected-(U$8-PadB7)") (class "Default")
      (node (ref "U$8") (pin "B7") (pinfunction "B7_B7") (pintype "bidirectional"))
    )
    (net (code "137") (name "unconnected-(U$8-PadB8)") (class "Default")
      (node (ref "U$8") (pin "B8") (pinfunction "B8_B8") (pintype "bidirectional"))
    )
    (net (code "138") (name "unconnected-(U$8-PadB9)") (class "Default")
      (node (ref "U$8") (pin "B9") (pinfunction "B9_B9") (pintype "bidirectional"))
    )
    (net (code "139") (name "unconnected-(U$8-PadB10)") (class "Default")
      (node (ref "U$8") (pin "B10") (pinfunction "B10_B10") (pintype "bidirectional"))
    )
    (net (code "140") (name "unconnected-(U$8-PadB11)") (class "Default")
      (node (ref "U$8") (pin "B11") (pinfunction "B11_B11") (pintype "bidirectional"))
    )
    (net (code "141") (name "unconnected-(U$8-PadB12)") (class "Default")
      (node (ref "U$8") (pin "B12") (pinfunction "B12_B12") (pintype "bidirectional"))
    )
    (net (code "142") (name "unconnected-(U$8-PadB13)") (class "Default")
      (node (ref "U$8") (pin "B13") (pinfunction "B13_B13") (pintype "bidirectional"))
    )
    (net (code "143") (name "unconnected-(U$8-PadB14)") (class "Default")
      (node (ref "U$8") (pin "B14") (pinfunction "B14_B14") (pintype "bidirectional"))
    )
    (net (code "144") (name "unconnected-(U$8-PadB15)") (class "Default")
      (node (ref "U$8") (pin "B15") (pinfunction "B15_B15") (pintype "bidirectional"))
    )
    (net (code "145") (name "unconnected-(U$8-PadB16)") (class "Default")
      (node (ref "U$8") (pin "B16") (pinfunction "B16_B16") (pintype "bidirectional"))
    )
    (net (code "146") (name "unconnected-(U$8-PadB17)") (class "Default")
      (node (ref "U$8") (pin "B17") (pinfunction "B17_B17") (pintype "bidirectional"))
    )
    (net (code "147") (name "unconnected-(U$8-PadB18)") (class "Default")
      (node (ref "U$8") (pin "B18") (pinfunction "B18_B18") (pintype "bidirectional"))
    )
    (net (code "148") (name "unconnected-(U$8-PadB19)") (class "Default")
      (node (ref "U$8") (pin "B19") (pinfunction "B19_B19") (pintype "bidirectional"))
    )
    (net (code "149") (name "unconnected-(U$8-PadB20)") (class "Default")
      (node (ref "U$8") (pin "B20") (pinfunction "B20_B20") (pintype "bidirectional"))
    )
    (net (code "150") (name "unconnected-(U$8-PadB21)") (class "Default")
      (node (ref "U$8") (pin "B21") (pinfunction "B21_B21") (pintype "bidirectional"))
    )
    (net (code "151") (name "unconnected-(U$8-PadB22)") (class "Default")
      (node (ref "U$8") (pin "B22") (pinfunction "B22_B22") (pintype "bidirectional"))
    )
    (net (code "152") (name "unconnected-(U$8-PadB23)") (class "Default")
      (node (ref "U$8") (pin "B23") (pinfunction "B23_B23") (pintype "bidirectional"))
    )
    (net (code "153") (name "unconnected-(U$8-PadB24)") (class "Default")
      (node (ref "U$8") (pin "B24") (pinfunction "B24_B24") (pintype "bidirectional"))
    )
    (net (code "154") (name "unconnected-(U$8-PadB25)") (class "Default")
      (node (ref "U$8") (pin "B25") (pinfunction "B25_B25") (pintype "bidirectional"))
    )
    (net (code "155") (name "unconnected-(U$8-PadB26)") (class "Default")
      (node (ref "U$8") (pin "B26") (pinfunction "B26_B26") (pintype "bidirectional"))
    )
    (net (code "156") (name "unconnected-(U$8-PadB27)") (class "Default")
      (node (ref "U$8") (pin "B27") (pinfunction "B27_B27") (pintype "bidirectional"))
    )
    (net (code "157") (name "unconnected-(U$8-PadB28)") (class "Default")
      (node (ref "U$8") (pin "B28") (pinfunction "B28_B28") (pintype "bidirectional"))
    )
    (net (code "158") (name "unconnected-(U$8-PadB29)") (class "Default")
      (node (ref "U$8") (pin "B29") (pinfunction "B29_B29") (pintype "bidirectional"))
    )
    (net (code "159") (name "unconnected-(U$8-PadB30)") (class "Default")
      (node (ref "U$8") (pin "B30") (pinfunction "B30_B30") (pintype "bidirectional"))
    )
    (net (code "160") (name "unconnected-(U$8-PadB31)") (class "Default")
      (node (ref "U$8") (pin "B31") (pinfunction "B31_B31") (pintype "bidirectional"))
    )
    (net (code "161") (name "unconnected-(U$8-PadB32)") (class "Default")
      (node (ref "U$8") (pin "B32") (pinfunction "B32_B32") (pintype "bidirectional"))
    )
    (net (code "162") (name "unconnected-(U$8-PadB33)") (class "Default")
      (node (ref "U$8") (pin "B33") (pinfunction "B33_B33") (pintype "bidirectional"))
    )
    (net (code "163") (name "unconnected-(U$8-PadB34)") (class "Default")
      (node (ref "U$8") (pin "B34") (pinfunction "B34_B34") (pintype "bidirectional"))
    )
    (net (code "164") (name "unconnected-(U$8-PadB37)") (class "Default")
      (node (ref "U$8") (pin "B37") (pinfunction "B37_B37") (pintype "bidirectional"))
    )
    (net (code "165") (name "unconnected-(U$8-PadB38)") (class "Default")
      (node (ref "U$8") (pin "B38") (pinfunction "B38_B38") (pintype "bidirectional"))
    )
    (net (code "166") (name "unconnected-(U$8-PadB39)") (class "Default")
      (node (ref "U$8") (pin "B39") (pinfunction "B39_B39") (pintype "bidirectional"))
    )
    (net (code "167") (name "unconnected-(U$8-PadB40)") (class "Default")
      (node (ref "U$8") (pin "B40") (pinfunction "B40_B40") (pintype "bidirectional"))
    )
    (net (code "168") (name "unconnected-(U$8-PadB41)") (class "Default")
      (node (ref "U$8") (pin "B41") (pinfunction "B41_B41") (pintype "bidirectional"))
    )
    (net (code "169") (name "unconnected-(U$8-PadB42)") (class "Default")
      (node (ref "U$8") (pin "B42") (pinfunction "B42_B42") (pintype "bidirectional"))
    )
    (net (code "170") (name "unconnected-(U$8-PadB43)") (class "Default")
      (node (ref "U$8") (pin "B43") (pinfunction "B43_B43") (pintype "bidirectional"))
    )
    (net (code "171") (name "unconnected-(U$8-PadB44)") (class "Default")
      (node (ref "U$8") (pin "B44") (pinfunction "B44_B44") (pintype "bidirectional"))
    )
    (net (code "172") (name "unconnected-(U$8-PadB45)") (class "Default")
      (node (ref "U$8") (pin "B45") (pinfunction "B45_B45") (pintype "bidirectional"))
    )
    (net (code "173") (name "unconnected-(U$8-PadB47)") (class "Default")
      (node (ref "U$8") (pin "B47") (pinfunction "B47_B47") (pintype "bidirectional"))
    )
    (net (code "174") (name "unconnected-(U$8-PadB48)") (class "Default")
      (node (ref "U$8") (pin "B48") (pinfunction "B48_B48") (pintype "bidirectional"))
    )
    (net (code "175") (name "unconnected-(U$8-PadB49)") (class "Default")
      (node (ref "U$8") (pin "B49") (pinfunction "B49_B49") (pintype "bidirectional"))
    )
    (net (code "176") (name "unconnected-(U$8-PadB50)") (class "Default")
      (node (ref "U$8") (pin "B50") (pinfunction "B50_B50") (pintype "bidirectional"))
    )
    (net (code "177") (name "unconnected-(U$8-PadB51)") (class "Default")
      (node (ref "U$8") (pin "B51") (pinfunction "B51_B51") (pintype "bidirectional"))
    )
    (net (code "178") (name "unconnected-(U$8-PadB52)") (class "Default")
      (node (ref "U$8") (pin "B52") (pinfunction "B52_B52") (pintype "bidirectional"))
    )
    (net (code "179") (name "unconnected-(U$8-PadB53)") (class "Default")
      (node (ref "U$8") (pin "B53") (pinfunction "B53_B53") (pintype "bidirectional"))
    )
    (net (code "180") (name "unconnected-(U$8-PadB54)") (class "Default")
      (node (ref "U$8") (pin "B54") (pinfunction "B54_B54") (pintype "bidirectional"))
    )
    (net (code "181") (name "unconnected-(U$8-PadB55)") (class "Default")
      (node (ref "U$8") (pin "B55") (pinfunction "B55_B55") (pintype "bidirectional"))
    )
    (net (code "182") (name "unconnected-(U$8-PadB56)") (class "Default")
      (node (ref "U$8") (pin "B56") (pinfunction "B56_B56") (pintype "bidirectional"))
    )
    (net (code "183") (name "unconnected-(U$8-PadB57)") (class "Default")
      (node (ref "U$8") (pin "B57") (pinfunction "B57_B57") (pintype "bidirectional"))
    )
    (net (code "184") (name "unconnected-(U$8-PadB58)") (class "Default")
      (node (ref "U$8") (pin "B58") (pinfunction "B58_B58") (pintype "bidirectional"))
    )
    (net (code "185") (name "unconnected-(U$8-PadB59)") (class "Default")
      (node (ref "U$8") (pin "B59") (pinfunction "B59_B59") (pintype "bidirectional"))
    )
    (net (code "186") (name "unconnected-(U$8-PadB60)") (class "Default")
      (node (ref "U$8") (pin "B60") (pinfunction "B60_B60") (pintype "bidirectional"))
    )
    (net (code "187") (name "unconnected-(U$8-PadT7)") (class "Default")
      (node (ref "U$8") (pin "T7") (pinfunction "T7_T7") (pintype "bidirectional"))
    )
    (net (code "188") (name "unconnected-(U$8-PadT8)") (class "Default")
      (node (ref "U$8") (pin "T8") (pinfunction "T8_T8") (pintype "bidirectional"))
    )
    (net (code "189") (name "unconnected-(U$8-PadT9)") (class "Default")
      (node (ref "U$8") (pin "T9") (pinfunction "T9_T9") (pintype "bidirectional"))
    )
    (net (code "190") (name "unconnected-(U$8-PadT10)") (class "Default")
      (node (ref "U$8") (pin "T10") (pinfunction "T10_T10") (pintype "bidirectional"))
    )
    (net (code "191") (name "unconnected-(U$8-PadT19)") (class "Default")
      (node (ref "U$8") (pin "T19") (pinfunction "T19_T19") (pintype "bidirectional"))
    )
    (net (code "192") (name "unconnected-(U$8-PadT20)") (class "Default")
      (node (ref "U$8") (pin "T20") (pinfunction "T20_T20") (pintype "bidirectional"))
    )
    (net (code "193") (name "unconnected-(U$8-PadT21)") (class "Default")
      (node (ref "U$8") (pin "T21") (pinfunction "T21_T21") (pintype "bidirectional"))
    )
    (net (code "194") (name "unconnected-(U$8-PadT22)") (class "Default")
      (node (ref "U$8") (pin "T22") (pinfunction "T22_T22") (pintype "bidirectional"))
    )
    (net (code "195") (name "unconnected-(U$8-PadT23)") (class "Default")
      (node (ref "U$8") (pin "T23") (pinfunction "T23_T23") (pintype "bidirectional"))
    )
    (net (code "196") (name "unconnected-(U$8-PadT24)") (class "Default")
      (node (ref "U$8") (pin "T24") (pinfunction "T24_T24") (pintype "bidirectional"))
    )
    (net (code "197") (name "unconnected-(U$8-PadT26)") (class "Default")
      (node (ref "U$8") (pin "T26") (pinfunction "T26_T26") (pintype "bidirectional"))
    )
    (net (code "198") (name "unconnected-(U$8-PadT27)") (class "Default")
      (node (ref "U$8") (pin "T27") (pinfunction "T27_T27") (pintype "bidirectional"))
    )
    (net (code "199") (name "unconnected-(U$8-PadT28)") (class "Default")
      (node (ref "U$8") (pin "T28") (pinfunction "T28_T28") (pintype "bidirectional"))
    )
    (net (code "200") (name "unconnected-(U$8-PadT29)") (class "Default")
      (node (ref "U$8") (pin "T29") (pinfunction "T29_T29") (pintype "bidirectional"))
    )
    (net (code "201") (name "unconnected-(U$8-PadT30)") (class "Default")
      (node (ref "U$8") (pin "T30") (pinfunction "T30_T30") (pintype "bidirectional"))
    )
    (net (code "202") (name "unconnected-(U$8-PadT35)") (class "Default")
      (node (ref "U$8") (pin "T35") (pinfunction "T35_T35") (pintype "bidirectional"))
    )
    (net (code "203") (name "unconnected-(U$8-PadT36)") (class "Default")
      (node (ref "U$8") (pin "T36") (pinfunction "T36_T36") (pintype "bidirectional"))
    )
    (net (code "204") (name "unconnected-(U$8-PadT40)") (class "Default")
      (node (ref "U$8") (pin "T40") (pinfunction "T40_T40") (pintype "bidirectional"))
    )
    (net (code "205") (name "unconnected-(U$8-PadT43)") (class "Default")
      (node (ref "U$8") (pin "T43") (pinfunction "T43_T43") (pintype "bidirectional"))
    )
    (net (code "206") (name "unconnected-(U$8-PadT44)") (class "Default")
      (node (ref "U$8") (pin "T44") (pinfunction "T44_T44") (pintype "bidirectional"))
    )
    (net (code "207") (name "unconnected-(U$8-PadT45)") (class "Default")
      (node (ref "U$8") (pin "T45") (pinfunction "T45_T45") (pintype "bidirectional"))
    )
    (net (code "208") (name "unconnected-(U$8-PadT46)") (class "Default")
      (node (ref "U$8") (pin "T46") (pinfunction "T46_T46") (pintype "bidirectional"))
    )
    (net (code "209") (name "unconnected-(U$8-PadT47)") (class "Default")
      (node (ref "U$8") (pin "T47") (pinfunction "T47_T47") (pintype "bidirectional"))
    )
    (net (code "210") (name "unconnected-(U$8-PadT48)") (class "Default")
      (node (ref "U$8") (pin "T48") (pinfunction "T48_T48") (pintype "bidirectional"))
    )
    (net (code "211") (name "unconnected-(U$8-PadT49)") (class "Default")
      (node (ref "U$8") (pin "T49") (pinfunction "T49_T49") (pintype "bidirectional"))
    )
    (net (code "212") (name "unconnected-(U$8-PadT50)") (class "Default")
      (node (ref "U$8") (pin "T50") (pinfunction "T50_T50") (pintype "bidirectional"))
    )
    (net (code "213") (name "unconnected-(U$8-PadT51)") (class "Default")
      (node (ref "U$8") (pin "T51") (pinfunction "T51_T51") (pintype "bidirectional"))
    )
    (net (code "214") (name "unconnected-(U$8-PadT52)") (class "Default")
      (node (ref "U$8") (pin "T52") (pinfunction "T52_T52") (pintype "bidirectional"))
    )
    (net (code "215") (name "unconnected-(U$8-PadT53)") (class "Default")
      (node (ref "U$8") (pin "T53") (pinfunction "T53_T53") (pintype "bidirectional"))
    )
    (net (code "216") (name "unconnected-(U$8-PadT54)") (class "Default")
      (node (ref "U$8") (pin "T54") (pinfunction "T54_T54") (pintype "bidirectional"))
    )
    (net (code "217") (name "unconnected-(U$8-PadT55)") (class "Default")
      (node (ref "U$8") (pin "T55") (pinfunction "T55_T55") (pintype "bidirectional"))
    )
    (net (code "218") (name "unconnected-(U$8-PadT56)") (class "Default")
      (node (ref "U$8") (pin "T56") (pinfunction "T56_T56") (pintype "bidirectional"))
    )
    (net (code "219") (name "unconnected-(U$8-PadT57)") (class "Default")
      (node (ref "U$8") (pin "T57") (pinfunction "T57_T57") (pintype "bidirectional"))
    )
    (net (code "220") (name "unconnected-(U$8-PadT58)") (class "Default")
      (node (ref "U$8") (pin "T58") (pinfunction "T58_T58") (pintype "bidirectional"))
    )
    (net (code "221") (name "unconnected-(U$8-PadT59)") (class "Default")
      (node (ref "U$8") (pin "T59") (pinfunction "T59_T59") (pintype "bidirectional"))
    )
  )
)
